# EEZ_CF-DIC_r5B1.net
KiCad netlist of a schematic drawn in EAGLE
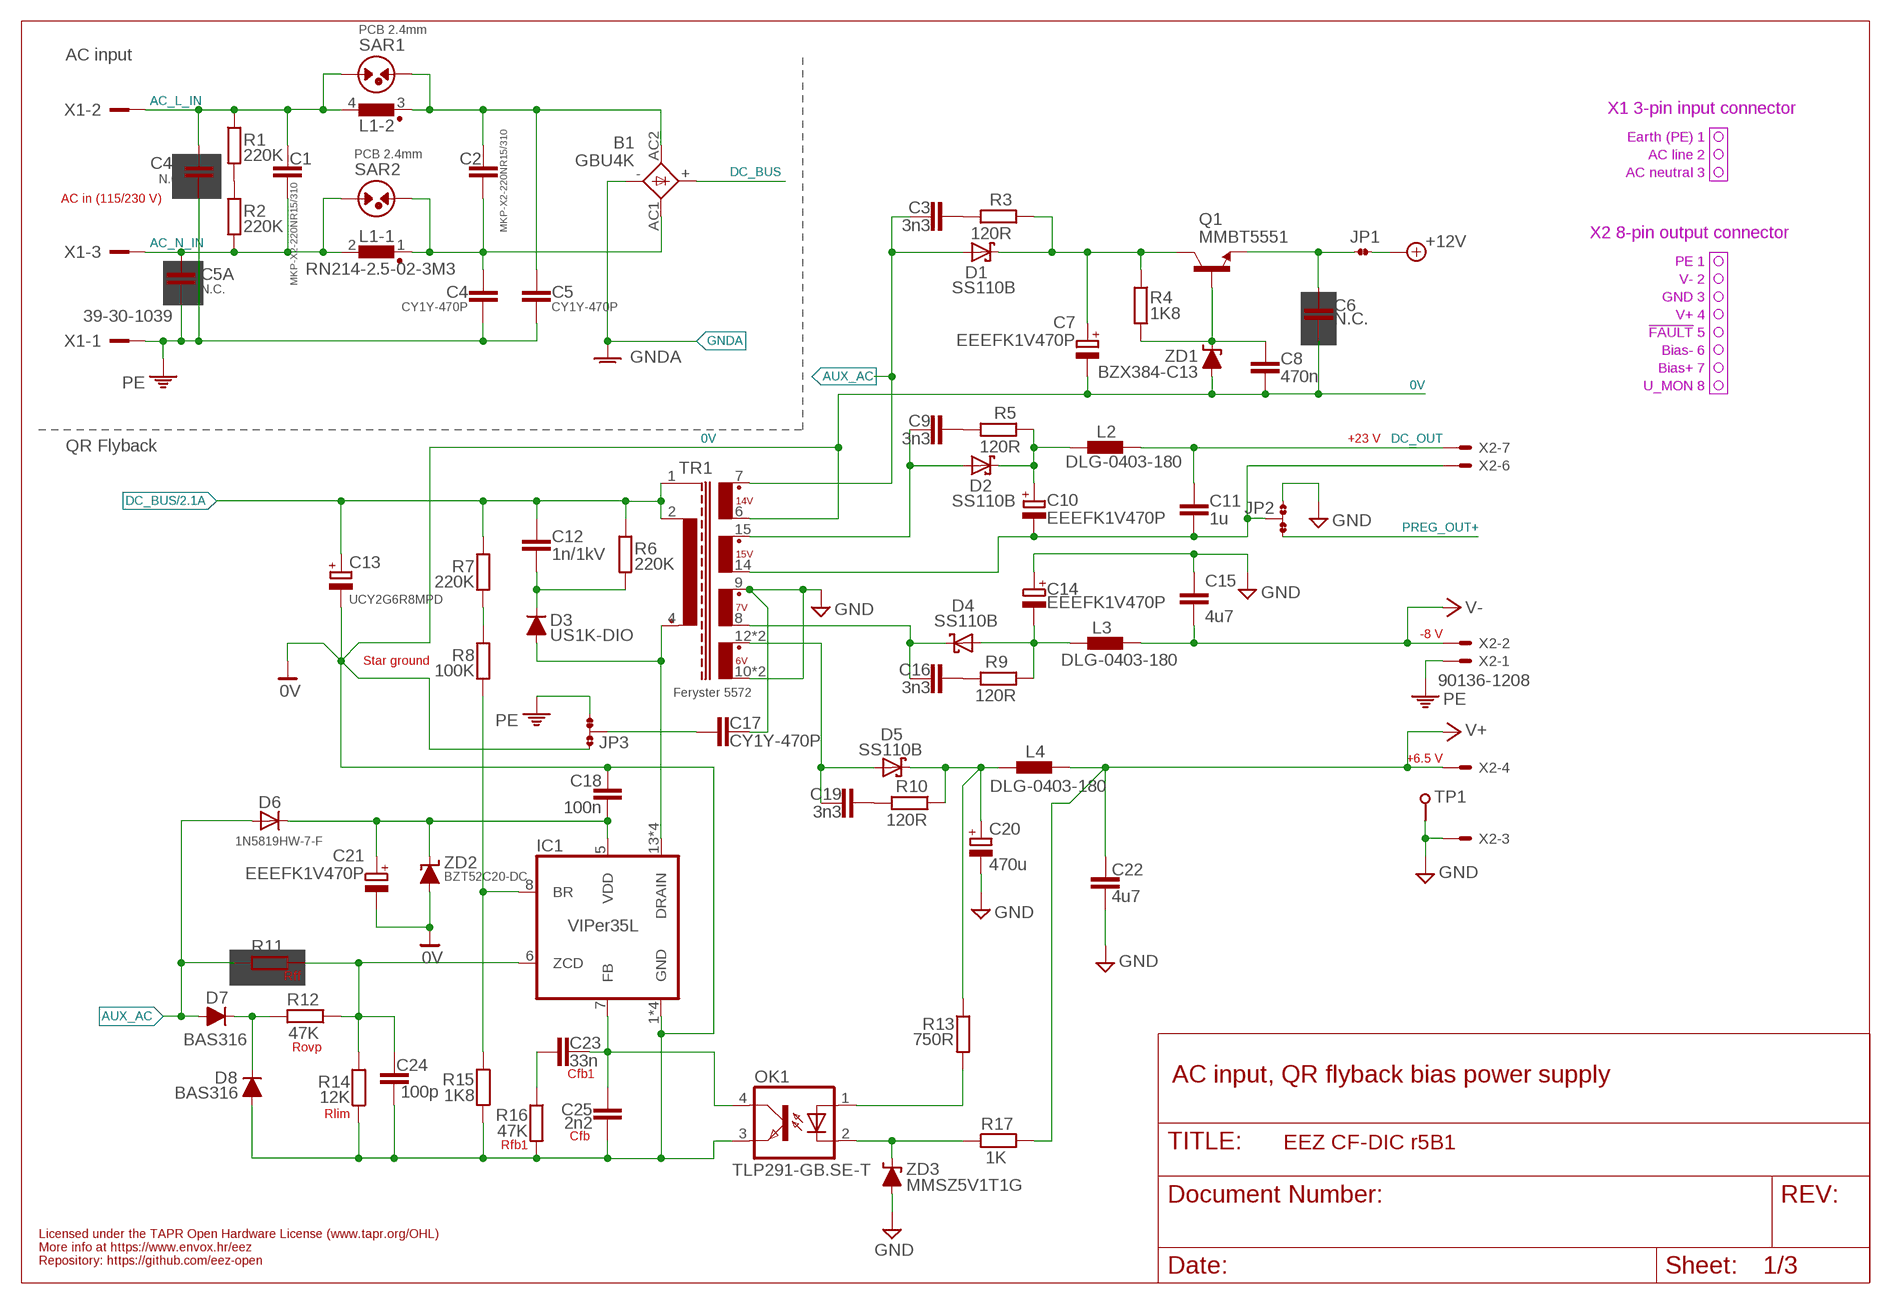
[diagram p0: schematic, sheet 1]
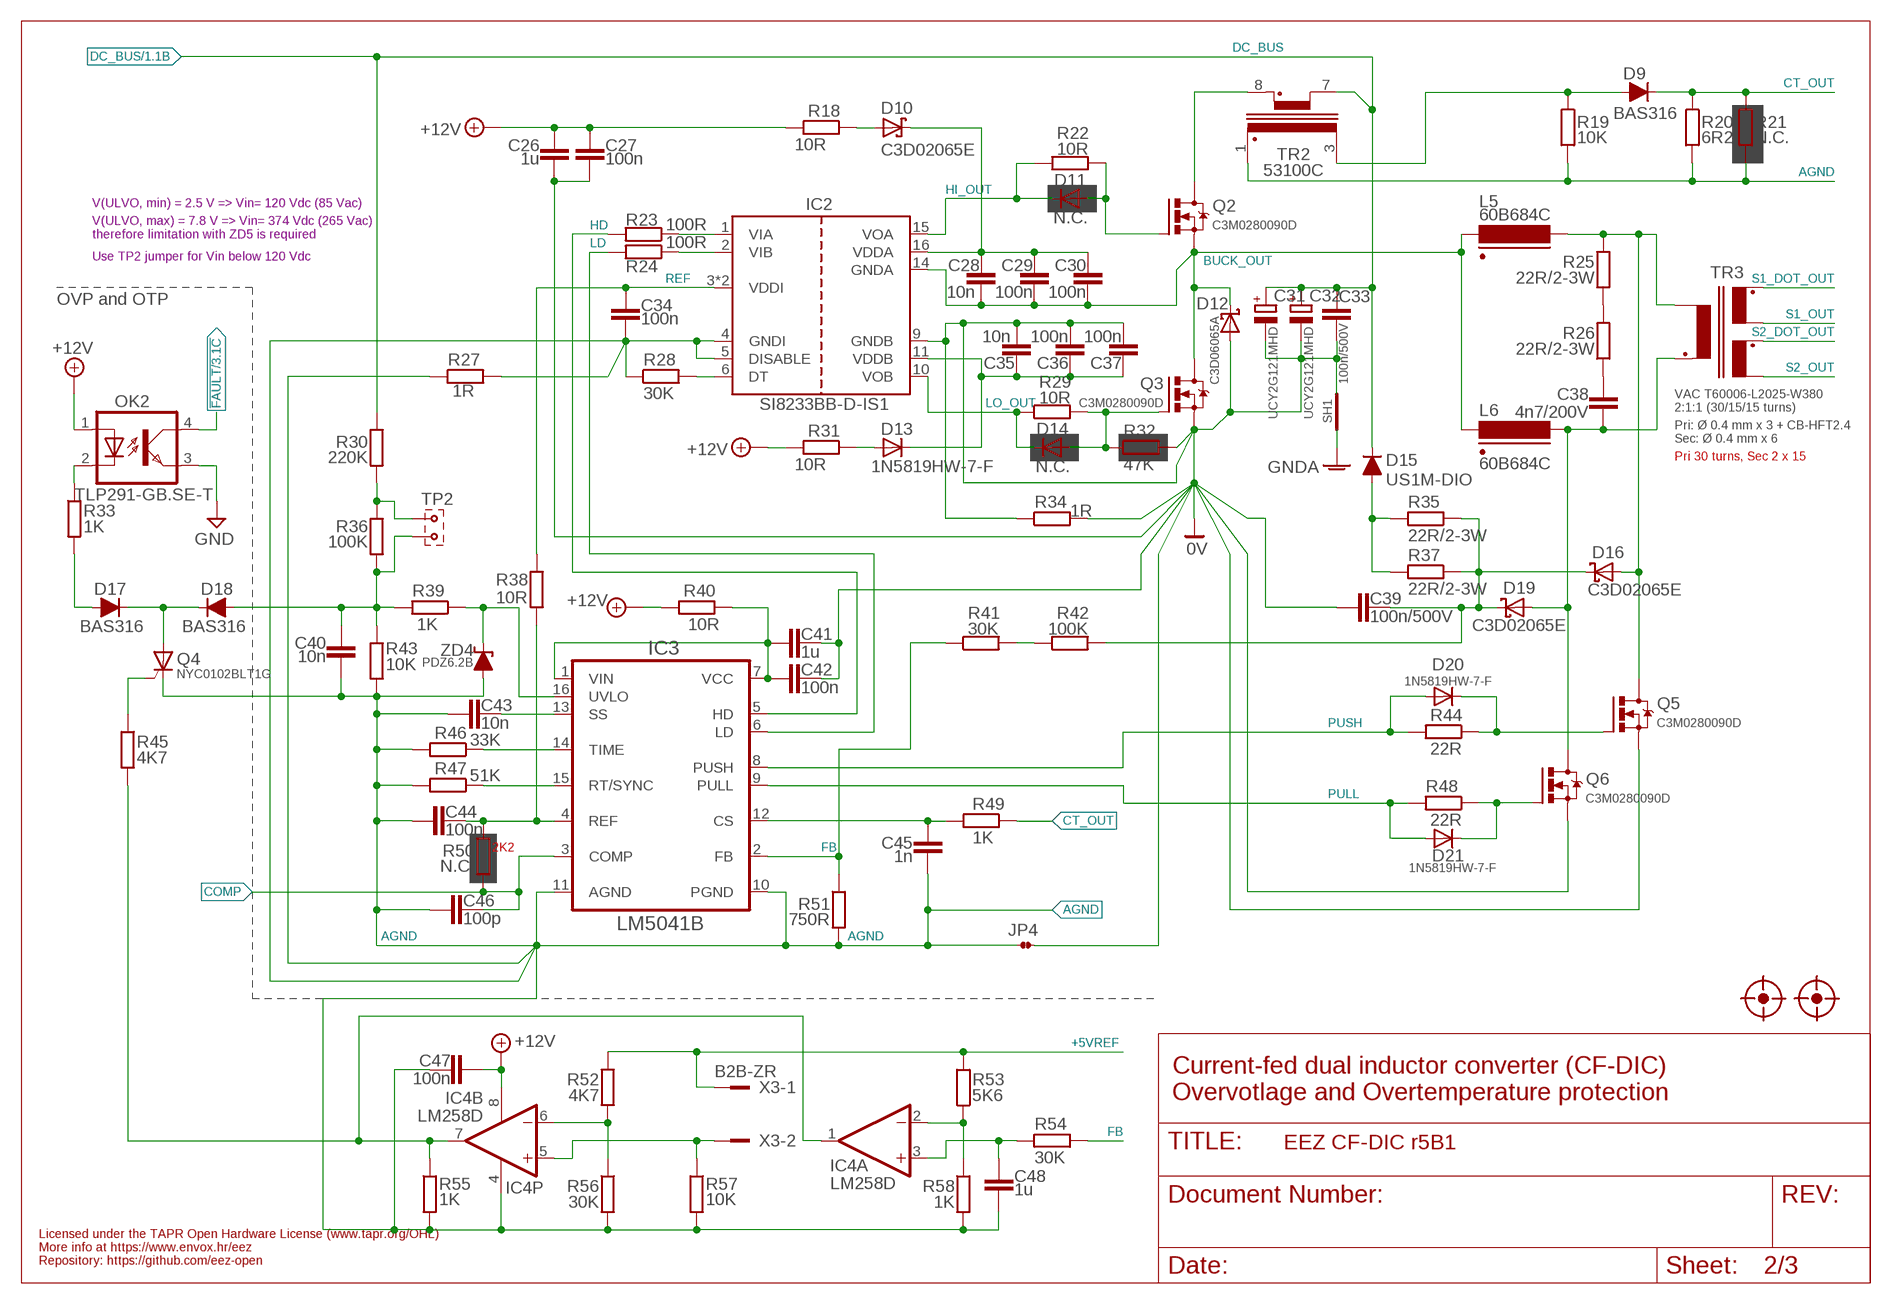
[diagram p1: schematic, sheet 2]
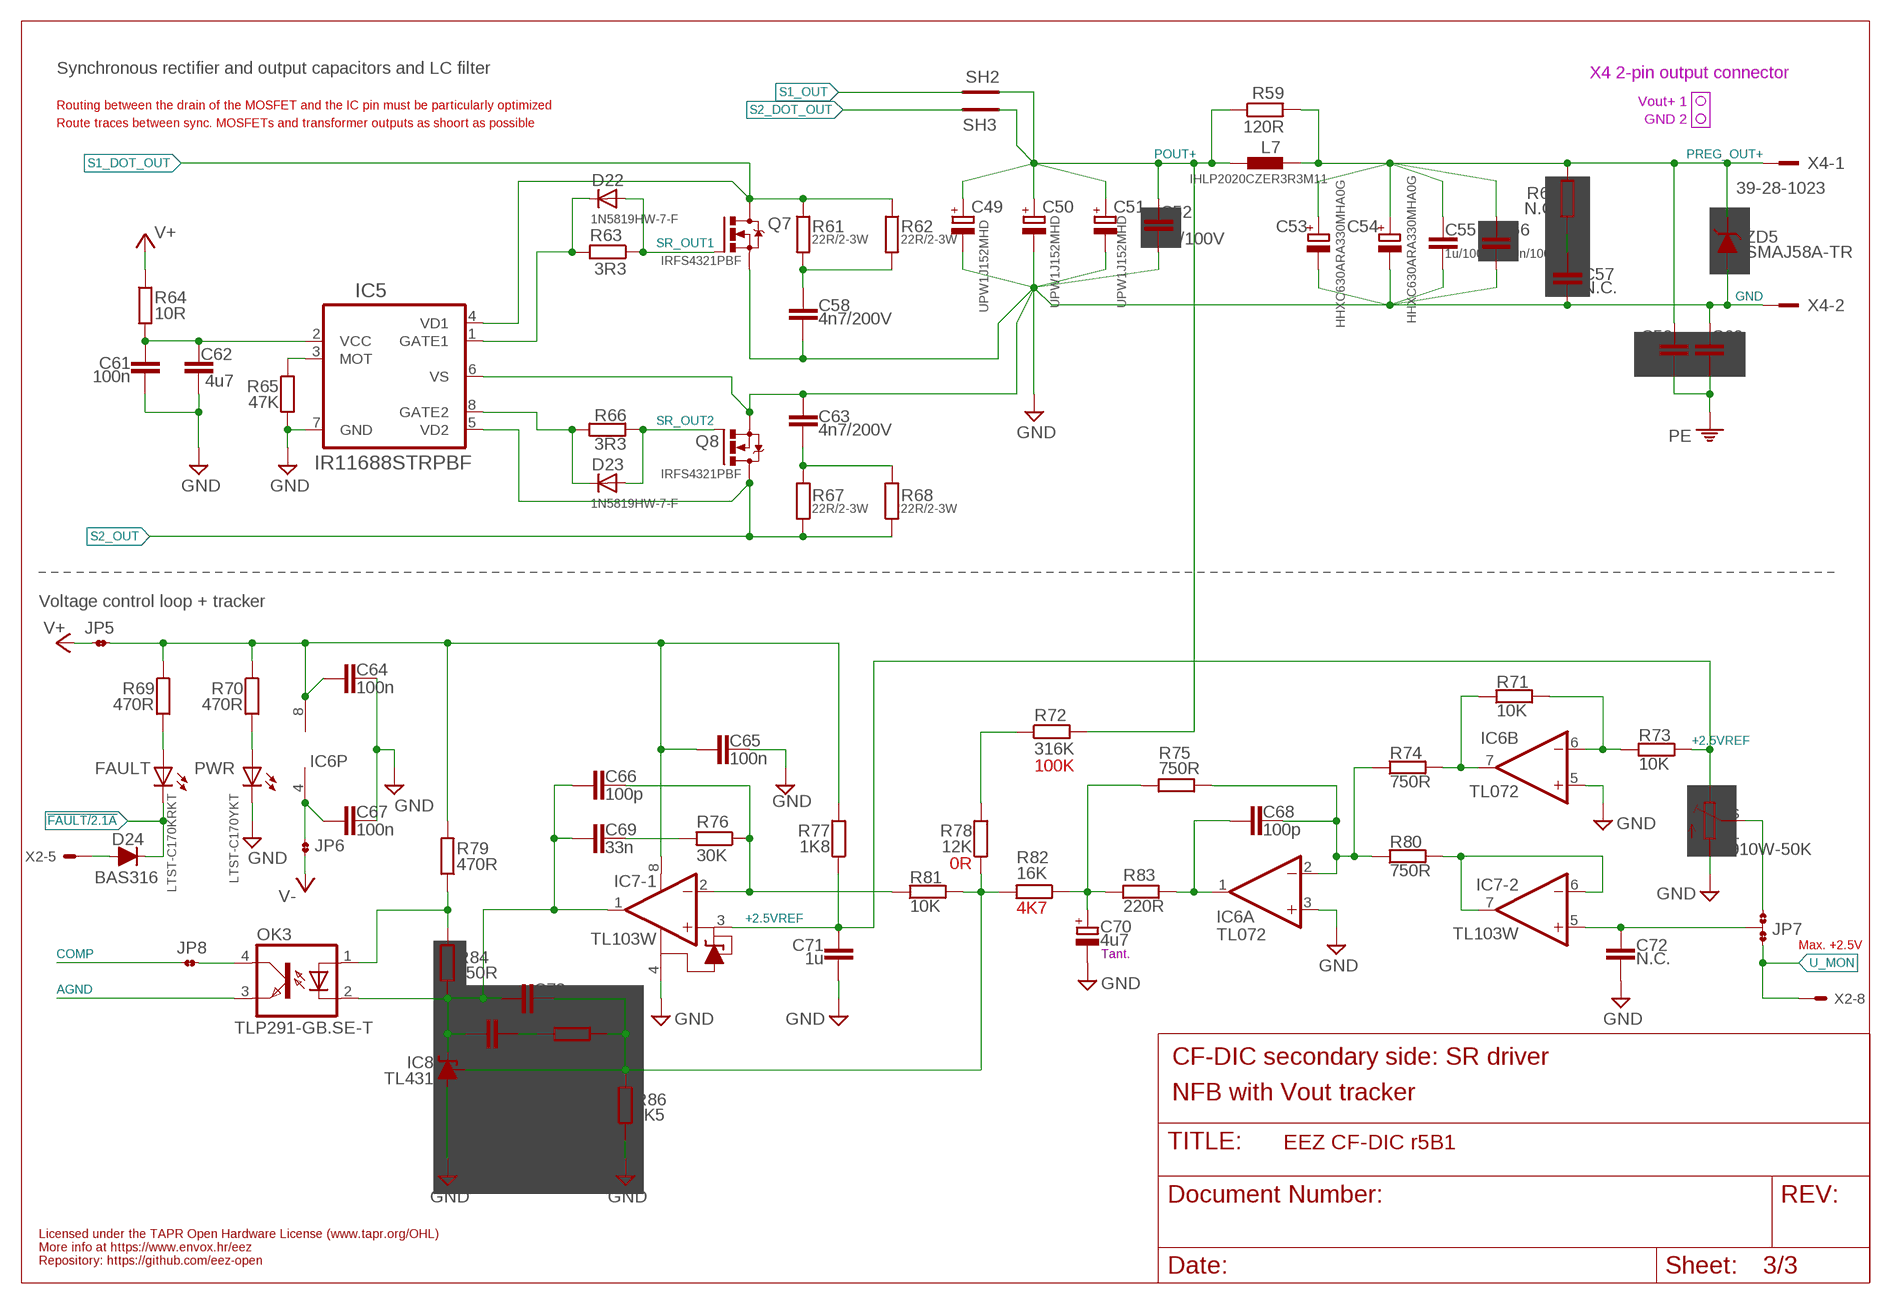
[diagram p2: schematic, sheet 3]

(export (version "E")
  (design (tool "Eeschema 10.0.6"))
  (components
    (comp (ref "C26")
      (value "1u")
      (footprint "eagle-import:C0805")
      (libsource (lib "eagle-import") (part "C-EUC0805"))
    )
    (comp (ref "C27")
      (value "100n")
      (footprint "eagle-import:C0603")
      (libsource (lib "eagle-import") (part "C-EUC0603"))
    )
    (comp (ref "C28")
      (value "10n")
      (footprint "eagle-import:C0603")
      (libsource (lib "eagle-import") (part "C-EUC0603"))
    )
    (comp (ref "C29")
      (value "100n")
      (footprint "eagle-import:C0603")
      (libsource (lib "eagle-import") (part "C-EUC0603"))
    )
    (comp (ref "C30")
      (value "100n")
      (footprint "eagle-import:C0603")
      (libsource (lib "eagle-import") (part "C-EUC0603"))
    )
    (comp (ref "C31")
      (value "UCY2G121MHD")
      (footprint "eagle-import:ECAP7.5_18")
      (libsource (lib "eagle-import") (part "ECAP7.5G_18MM"))
    )
    (comp (ref "C32")
      (value "UCY2G121MHD")
      (footprint "eagle-import:ECAP7.5_18")
      (libsource (lib "eagle-import") (part "ECAP7.5G_18MM"))
    )
    (comp (ref "C33")
      (value "100n/500V")
      (footprint "eagle-import:C1812")
      (libsource (lib "eagle-import") (part "C-EUC1812"))
    )
    (comp (ref "C34")
      (value "100n")
      (footprint "eagle-import:C0603")
      (libsource (lib "eagle-import") (part "C-EUC0603"))
    )
    (comp (ref "C35")
      (value "10n")
      (footprint "eagle-import:C0603")
      (libsource (lib "eagle-import") (part "C-EUC0603"))
    )
    (comp (ref "C36")
      (value "100n")
      (footprint "eagle-import:C0603")
      (libsource (lib "eagle-import") (part "C-EUC0603"))
    )
    (comp (ref "C37")
      (value "100n")
      (footprint "eagle-import:C0603")
      (libsource (lib "eagle-import") (part "C-EUC0603"))
    )
    (comp (ref "C38")
      (value "4n7/200V")
      (footprint "eagle-import:C1210")
      (libsource (lib "eagle-import") (part "C-EUC1210"))
    )
    (comp (ref "C39")
      (value "100n/500V")
      (footprint "eagle-import:C1812")
      (libsource (lib "eagle-import") (part "C-EUC1812"))
    )
    (comp (ref "C40")
      (value "10n")
      (footprint "eagle-import:C0805")
      (libsource (lib "eagle-import") (part "C-EUC0805"))
    )
    (comp (ref "C41")
      (value "1u")
      (footprint "eagle-import:C0805")
      (libsource (lib "eagle-import") (part "C-EUC0805"))
    )
    (comp (ref "C42")
      (value "100n")
      (footprint "eagle-import:C0603")
      (libsource (lib "eagle-import") (part "C-EUC0603"))
    )
    (comp (ref "C43")
      (value "10n")
      (footprint "eagle-import:C0805")
      (libsource (lib "eagle-import") (part "C-EUC0805"))
    )
    (comp (ref "C44")
      (value "100n")
      (footprint "eagle-import:C0603")
      (libsource (lib "eagle-import") (part "C-EUC0603"))
    )
    (comp (ref "C45")
      (value "1n")
      (footprint "eagle-import:C0805")
      (libsource (lib "eagle-import") (part "C-EUC0805"))
    )
    (comp (ref "C46")
      (value "100p")
      (footprint "eagle-import:C0805")
      (libsource (lib "eagle-import") (part "C-EUC0805"))
    )
    (comp (ref "C47")
      (value "100n")
      (footprint "eagle-import:C0603")
      (libsource (lib "eagle-import") (part "C-EUC0603"))
    )
    (comp (ref "C48")
      (value "1u")
      (footprint "eagle-import:C0805")
      (libsource (lib "eagle-import") (part "C-EUC0805"))
    )
    (comp (ref "D9")
      (value "BAS316")
      (footprint "eagle-import:SOD323-R")
      (libsource (lib "eagle-import") (part "DIODESOD323R"))
    )
    (comp (ref "D10")
      (value "C3D02065E")
      (footprint "eagle-import:TO252")
      (libsource (lib "eagle-import") (part "SCHOTTKY-SIC"))
    )
    (comp (ref "D11")
      (value "N.C.")
      (footprint "eagle-import:SOD323-W")
      (libsource (lib "eagle-import") (part "DIODE-SOD323-W"))
    )
    (comp (ref "D12")
      (value "C3D06065A")
      (footprint "eagle-import:TO220-2")
      (libsource (lib "eagle-import") (part "SCHOTTKY-TO220"))
    )
    (comp (ref "D13")
      (value "1N5819HW-7-F")
      (footprint "eagle-import:SOD323-W")
      (libsource (lib "eagle-import") (part "DIODE-SOD323-W"))
    )
    (comp (ref "D14")
      (value "N.C.")
      (footprint "eagle-import:SOD323-W")
      (libsource (lib "eagle-import") (part "DIODE-SOD323-W"))
    )
    (comp (ref "D15")
      (value "US1M-DIO")
      (footprint "eagle-import:DO214AA")
      (libsource (lib "eagle-import") (part "DIODEDO214AA"))
    )
    (comp (ref "D16")
      (value "C3D02065E")
      (footprint "eagle-import:TO252")
      (libsource (lib "eagle-import") (part "SCHOTTKY-SIC"))
    )
    (comp (ref "D17")
      (value "BAS316")
      (footprint "eagle-import:SOD323-R")
      (libsource (lib "eagle-import") (part "DIODESOD323R"))
    )
    (comp (ref "D18")
      (value "BAS316")
      (footprint "eagle-import:SOD323-R")
      (libsource (lib "eagle-import") (part "DIODESOD323R"))
    )
    (comp (ref "D19")
      (value "C3D02065E")
      (footprint "eagle-import:TO252")
      (libsource (lib "eagle-import") (part "SCHOTTKY-SIC"))
    )
    (comp (ref "D20")
      (value "1N5819HW-7-F")
      (footprint "eagle-import:SOD323-W")
      (libsource (lib "eagle-import") (part "DIODE-SOD323-W"))
    )
    (comp (ref "D21")
      (value "1N5819HW-7-F")
      (footprint "eagle-import:SOD323-W")
      (libsource (lib "eagle-import") (part "DIODE-SOD323-W"))
    )
    (comp (ref "FM1")
      (value "FIDUCIAL_2")
      (footprint "eagle-import:FIDUCIAL_DUAL")
      (libsource (lib "eagle-import") (part "FIDUCIAL_2"))
    )
    (comp (ref "FM2")
      (value "FIDUCIAL_2")
      (footprint "eagle-import:FIDUCIAL_DUAL")
      (libsource (lib "eagle-import") (part "FIDUCIAL_2"))
    )
    (comp (ref "IC2")
      (value "SI8233BB-D-IS1")
      (footprint "eagle-import:SOIC-16")
      (libsource (lib "eagle-import") (part "SI8233"))
    )
    (comp (ref "IC3")
      (value "LM5041B")
      (footprint "eagle-import:MTC16")
      (fields (field (name "MANUFACTURER_PART_NUMBER") "lm5041mtcnopb"))
      (libsource (lib "eagle-import") (part "LM5041"))
    )
    (comp (ref "IC4")
      (value "LM258D")
      (footprint "eagle-import:SOIC127P600X173-8N")
      (libsource (lib "eagle-import") (part "TL072SOIC8"))
    )
    (comp (ref "JP4")
      (value "JP2-NOCUT")
      (footprint "eagle-import:JP2-NOCUT")
      (libsource (lib "eagle-import") (part "JP2-NOCUT"))
    )
    (comp (ref "L5")
      (value "60B684C")
      (footprint "eagle-import:MURATA_6000B")
      (libsource (lib "eagle-import") (part "MURATA_6000B"))
    )
    (comp (ref "L6")
      (value "60B684C")
      (footprint "eagle-import:MURATA_6000B")
      (libsource (lib "eagle-import") (part "MURATA_6000B"))
    )
    (comp (ref "OK2")
      (value "TLP291-GB.SE-T")
      (footprint "eagle-import:SO4")
      (libsource (lib "eagle-import") (part "TLP291"))
    )
    (comp (ref "Q2")
      (value "C3M0280090D")
      (footprint "eagle-import:TO247BV")
      (libsource (lib "eagle-import") (part "IRFP240"))
    )
    (comp (ref "Q3")
      (value "C3M0280090D")
      (footprint "eagle-import:TO247BV")
      (libsource (lib "eagle-import") (part "IRFP240"))
    )
    (comp (ref "Q4")
      (value "NYC0102BLT1G")
      (footprint "eagle-import:SOT23")
      (libsource (lib "eagle-import") (part "NYC0102BLT1G"))
    )
    (comp (ref "Q5")
      (value "C3M0280090D")
      (footprint "eagle-import:TO247BV")
      (libsource (lib "eagle-import") (part "IRFP240"))
    )
    (comp (ref "Q6")
      (value "C3M0280090D")
      (footprint "eagle-import:TO247BV")
      (libsource (lib "eagle-import") (part "IRFP240"))
    )
    (comp (ref "R18")
      (value "10R")
      (footprint "eagle-import:R0805")
      (libsource (lib "eagle-import") (part "R-EU_R0805"))
    )
    (comp (ref "R19")
      (value "10K")
      (footprint "eagle-import:R0805")
      (libsource (lib "eagle-import") (part "R-EU_R0805"))
    )
    (comp (ref "R20")
      (value "6R2")
      (footprint "eagle-import:R0805")
      (libsource (lib "eagle-import") (part "R-EU_R0805"))
    )
    (comp (ref "R21")
      (value "N.C.")
      (footprint "eagle-import:R0805")
      (libsource (lib "eagle-import") (part "R-EU_R0805"))
    )
    (comp (ref "R22")
      (value "10R")
      (footprint "eagle-import:R0805")
      (libsource (lib "eagle-import") (part "R-EU_R0805"))
    )
    (comp (ref "R23")
      (value "100R")
      (footprint "eagle-import:R0805")
      (libsource (lib "eagle-import") (part "R-EU_R0805"))
    )
    (comp (ref "R24")
      (value "100R")
      (footprint "eagle-import:R0805")
      (libsource (lib "eagle-import") (part "R-EU_R0805"))
    )
    (comp (ref "R25")
      (value "22R/2-3W")
      (footprint "eagle-import:R2512")
      (libsource (lib "eagle-import") (part "R-EU_R2512"))
    )
    (comp (ref "R26")
      (value "22R/2-3W")
      (footprint "eagle-import:R2512")
      (libsource (lib "eagle-import") (part "R-EU_R2512"))
    )
    (comp (ref "R27")
      (value "1R")
      (footprint "eagle-import:R0805")
      (libsource (lib "eagle-import") (part "R-EU_R0805"))
    )
    (comp (ref "R28")
      (value "30K")
      (footprint "eagle-import:R0805")
      (libsource (lib "eagle-import") (part "R-EU_R0805"))
    )
    (comp (ref "R29")
      (value "10R")
      (footprint "eagle-import:R0805")
      (libsource (lib "eagle-import") (part "R-EU_R0805"))
    )
    (comp (ref "R30")
      (value "220K")
      (footprint "eagle-import:R1206")
      (libsource (lib "eagle-import") (part "R-EU_R1206"))
    )
    (comp (ref "R31")
      (value "10R")
      (footprint "eagle-import:R0805")
      (libsource (lib "eagle-import") (part "R-EU_R0805"))
    )
    (comp (ref "R32")
      (value "47K")
      (footprint "eagle-import:R0805")
      (libsource (lib "eagle-import") (part "R-EU_R0805"))
    )
    (comp (ref "R33")
      (value "1K")
      (footprint "eagle-import:R0805")
      (libsource (lib "eagle-import") (part "R-EU_R0805"))
    )
    (comp (ref "R34")
      (value "1R")
      (footprint "eagle-import:R0805")
      (libsource (lib "eagle-import") (part "R-EU_R0805"))
    )
    (comp (ref "R35")
      (value "22R/2-3W")
      (footprint "eagle-import:R2512")
      (libsource (lib "eagle-import") (part "R-EU_R2512"))
    )
    (comp (ref "R36")
      (value "100K")
      (footprint "eagle-import:R0805")
      (libsource (lib "eagle-import") (part "R-EU_R0805"))
    )
    (comp (ref "R37")
      (value "22R/2-3W")
      (footprint "eagle-import:R2512")
      (libsource (lib "eagle-import") (part "R-EU_R2512"))
    )
    (comp (ref "R38")
      (value "10R")
      (footprint "eagle-import:R0805")
      (libsource (lib "eagle-import") (part "R-EU_R0805"))
    )
    (comp (ref "R39")
      (value "1K")
      (footprint "eagle-import:R0805")
      (libsource (lib "eagle-import") (part "R-EU_R0805"))
    )
    (comp (ref "R40")
      (value "10R")
      (footprint "eagle-import:R0805")
      (libsource (lib "eagle-import") (part "R-EU_R0805"))
    )
    (comp (ref "R41")
      (value "30K")
      (footprint "eagle-import:R0805")
      (libsource (lib "eagle-import") (part "R-EU_R0805"))
    )
    (comp (ref "R42")
      (value "100K")
      (footprint "eagle-import:R0805")
      (libsource (lib "eagle-import") (part "R-EU_R0805"))
    )
    (comp (ref "R43")
      (value "10K")
      (footprint "eagle-import:R0805")
      (libsource (lib "eagle-import") (part "R-EU_R0805"))
    )
    (comp (ref "R44")
      (value "22R")
      (footprint "eagle-import:R0805")
      (libsource (lib "eagle-import") (part "R-EU_R0805"))
    )
    (comp (ref "R45")
      (value "4K7")
      (footprint "eagle-import:R0805")
      (libsource (lib "eagle-import") (part "R-EU_R0805"))
    )
    (comp (ref "R46")
      (value "33K")
      (footprint "eagle-import:R0805")
      (libsource (lib "eagle-import") (part "R-EU_R0805"))
    )
    (comp (ref "R47")
      (value "51K")
      (footprint "eagle-import:R0805")
      (libsource (lib "eagle-import") (part "R-EU_R0805"))
    )
    (comp (ref "R48")
      (value "22R")
      (footprint "eagle-import:R0805")
      (libsource (lib "eagle-import") (part "R-EU_R0805"))
    )
    (comp (ref "R49")
      (value "1K")
      (footprint "eagle-import:R0805")
      (libsource (lib "eagle-import") (part "R-EU_R0805"))
    )
    (comp (ref "R50")
      (value "N.C.")
      (footprint "eagle-import:R0805")
      (libsource (lib "eagle-import") (part "R-EU_R0805"))
    )
    (comp (ref "R51")
      (value "750R")
      (footprint "eagle-import:R0805")
      (libsource (lib "eagle-import") (part "R-EU_R0805"))
    )
    (comp (ref "R52")
      (value "4K7")
      (footprint "eagle-import:R0805")
      (libsource (lib "eagle-import") (part "R-EU_R0805"))
    )
    (comp (ref "R53")
      (value "5K6")
      (footprint "eagle-import:R0805")
      (libsource (lib "eagle-import") (part "R-EU_R0805"))
    )
    (comp (ref "R54")
      (value "30K")
      (footprint "eagle-import:R0805")
      (libsource (lib "eagle-import") (part "R-EU_R0805"))
    )
    (comp (ref "R55")
      (value "1K")
      (footprint "eagle-import:R0805")
      (libsource (lib "eagle-import") (part "R-EU_R0805"))
    )
    (comp (ref "R56")
      (value "30K")
      (footprint "eagle-import:R0805")
      (libsource (lib "eagle-import") (part "R-EU_R0805"))
    )
    (comp (ref "R57")
      (value "10K")
      (footprint "eagle-import:R0805")
      (libsource (lib "eagle-import") (part "R-EU_R0805"))
    )
    (comp (ref "R58")
      (value "1K")
      (footprint "eagle-import:R0805")
      (libsource (lib "eagle-import") (part "R-EU_R0805"))
    )
    (comp (ref "SH1")
      (value "SHORTNOHOLE")
      (footprint "eagle-import:SHORT_NOHOLE")
      (libsource (lib "eagle-import") (part "SHORTNOHOLE"))
    )
    (comp (ref "TP2")
      (value "JUMPER-2PIN-2MM")
      (footprint "eagle-import:2MM-2")
      (libsource (lib "eagle-import") (part "JUMPER-2PIN-2MM"))
    )
    (comp (ref "TR2")
      (value "53100C")
      (footprint "eagle-import:MURATA_5300")
      (libsource (lib "eagle-import") (part "MURATA_5300"))
    )
    (comp (ref "TR3")
      (value "VAC T60006-L2025-W380")
      (footprint "eagle-import:VAC_DUAL_SEC")
      (libsource (lib "eagle-import") (part "PCB_TRAFO_FLYBACK2-VAC"))
    )
    (comp (ref "X3")
      (value "B2B-ZR")
      (footprint "eagle-import:B2B-ZR")
      (libsource (lib "eagle-import") (part "B2B-ZR"))
    )
    (comp (ref "ZD4")
      (value "PDZ6.2B")
      (footprint "eagle-import:SOD323-W")
      (libsource (lib "eagle-import") (part "ZENER-DIODESOD323"))
    )
    (comp (ref "C49")
      (value "UPW1J152MHD")
      (footprint "eagle-import:ECAP7.5_18")
      (libsource (lib "eagle-import") (part "ECAP7.5G_18MM"))
    )
    (comp (ref "C50")
      (value "UPW1J152MHD")
      (footprint "eagle-import:ECAP7.5_18")
      (libsource (lib "eagle-import") (part "ECAP7.5G_18MM"))
    )
    (comp (ref "C51")
      (value "UPW1J152MHD")
      (footprint "eagle-import:ECAP7.5_18")
      (libsource (lib "eagle-import") (part "ECAP7.5G_18MM"))
    )
    (comp (ref "C52")
      (value "1u/100V")
      (footprint "eagle-import:C1206")
      (libsource (lib "eagle-import") (part "C-EUC1206"))
    )
    (comp (ref "C53")
      (value "HHXC630ARA330MHA0G ")
      (footprint "eagle-import:CAPAE830X1050N")
      (fields
        (field (name "MPN") "EEE-FK1J470P")
        (field (name "TOLERANCE") "±20 %")
        (field (name "MPN_1") "EEE-FK1J470P")
        (field (name "OC_FARNELL") "9696032  ")
        (field (name "OC_NEWARK") "96K9403")
        (field (name "PACKAGE") "CASE-F")
        (field (name "SUPPLIER") "PANASONIC")
        (field (name "TOLERANCE_1") "±20 %")
        (field (name "VOLTAGERATING") "63 V")
      )
      (libsource (lib "eagle-import") (part "EEE--CASE-FFK1J470P"))
    )
    (comp (ref "C54")
      (value "HHXC630ARA330MHA0G")
      (footprint "eagle-import:CAPAE830X1050N")
      (fields (field (name "MPN") "EEE-FK1J470P") (field (name "TOLERANCE") "±20 %"))
      (libsource (lib "eagle-import") (part "EEE--CASE-FFK1J470P"))
    )
    (comp (ref "C55")
      (value "1u/100V")
      (footprint "eagle-import:C1206")
      (libsource (lib "eagle-import") (part "C-EUC1206"))
    )
    (comp (ref "C56")
      (value "100n/100V")
      (footprint "eagle-import:C1206")
      (libsource (lib "eagle-import") (part "C-EUC1206"))
    )
    (comp (ref "C57")
      (value "N.C.")
      (footprint "eagle-import:C1206")
      (libsource (lib "eagle-import") (part "C-EUC1206"))
    )
    (comp (ref "C58")
      (value "4n7/200V")
      (footprint "eagle-import:C1206")
      (libsource (lib "eagle-import") (part "C-EUC1206"))
    )
    (comp (ref "C59")
      (value "N.C.")
      (footprint "eagle-import:C1206")
      (libsource (lib "eagle-import") (part "C-EUC1206"))
    )
    (comp (ref "C60")
      (value "N.C.")
      (footprint "eagle-import:C1206")
      (libsource (lib "eagle-import") (part "C-EUC1206"))
    )
    (comp (ref "C61")
      (value "100n")
      (footprint "eagle-import:C0603")
      (libsource (lib "eagle-import") (part "C-EUC0603"))
    )
    (comp (ref "C62")
      (value "4u7")
      (footprint "eagle-import:C1206")
      (libsource (lib "eagle-import") (part "C-EUC1206"))
    )
    (comp (ref "C63")
      (value "4n7/200V")
      (footprint "eagle-import:C1206")
      (libsource (lib "eagle-import") (part "C-EUC1206"))
    )
    (comp (ref "C64")
      (value "100n")
      (footprint "eagle-import:C0603")
      (libsource (lib "eagle-import") (part "C-EUC0603"))
    )
    (comp (ref "C65")
      (value "100n")
      (footprint "eagle-import:C0603")
      (libsource (lib "eagle-import") (part "C-EUC0603"))
    )
    (comp (ref "C66")
      (value "100p")
      (footprint "eagle-import:C0805")
      (libsource (lib "eagle-import") (part "C-EUC0805"))
    )
    (comp (ref "C67")
      (value "100n")
      (footprint "eagle-import:C0603")
      (libsource (lib "eagle-import") (part "C-EUC0603"))
    )
    (comp (ref "C68")
      (value "100p")
      (footprint "eagle-import:C0805")
      (libsource (lib "eagle-import") (part "C-EUC0805"))
    )
    (comp (ref "C69")
      (value "33n")
      (footprint "eagle-import:C0805")
      (libsource (lib "eagle-import") (part "C-EUC0805"))
    )
    (comp (ref "C70")
      (value "4u7")
      (footprint "eagle-import:EC1206")
      (libsource (lib "eagle-import") (part "ECAP1206"))
    )
    (comp (ref "C71")
      (value "1u")
      (footprint "eagle-import:C0805")
      (libsource (lib "eagle-import") (part "C-EUC0805"))
    )
    (comp (ref "C72")
      (value "N.C.")
      (footprint "eagle-import:C0805")
      (libsource (lib "eagle-import") (part "C-EUC0805"))
    )
    (comp (ref "C73")
      (value "N.C.")
      (footprint "eagle-import:C0805")
      (libsource (lib "eagle-import") (part "C-EUC0805"))
    )
    (comp (ref "C74")
      (value "1n")
      (footprint "eagle-import:C0805")
      (libsource (lib "eagle-import") (part "C-EUC0805"))
    )
    (comp (ref "D22")
      (value "1N5819HW-7-F")
      (footprint "eagle-import:SOD323-W")
      (libsource (lib "eagle-import") (part "DIODE-SOD323-W"))
    )
    (comp (ref "D23")
      (value "1N5819HW-7-F")
      (footprint "eagle-import:SOD323-W")
      (libsource (lib "eagle-import") (part "DIODE-SOD323-W"))
    )
    (comp (ref "D24")
      (value "BAS316")
      (footprint "eagle-import:SOD323-R")
      (libsource (lib "eagle-import") (part "DIODESOD323R"))
    )
    (comp (ref "FAULT")
      (value "LTST-C170KRKT")
      (footprint "eagle-import:LED_0805")
      (libsource (lib "eagle-import") (part "LED0805"))
    )
    (comp (ref "IC5")
      (value "IR11688STRPBF")
      (footprint "eagle-import:SO8")
      (libsource (lib "eagle-import") (part "IR11688"))
    )
    (comp (ref "IC6")
      (value "TL072")
      (footprint "eagle-import:SOIC127P600X173-8N")
      (libsource (lib "eagle-import") (part "TL072SOIC8"))
    )
    (comp (ref "IC7")
      (value "TL103W")
      (footprint "eagle-import:SOIC127P600X173-8N")
      (libsource (lib "eagle-import") (part "TL103W"))
    )
    (comp (ref "IC8")
      (value "TL431")
      (footprint "eagle-import:SOT103P240X110-3N")
      (libsource (lib "eagle-import") (part "TL431"))
    )
    (comp (ref "JP5")
      (value "JP2-NOCUT")
      (footprint "eagle-import:JP2-NOCUT")
      (libsource (lib "eagle-import") (part "JP2-NOCUT"))
    )
    (comp (ref "JP6")
      (value "JP2-NOCUT")
      (footprint "eagle-import:JP2-NOCUT")
      (libsource (lib "eagle-import") (part "JP2-NOCUT"))
    )
    (comp (ref "JP7")
      (value "JP3-CUT")
      (footprint "eagle-import:JP3-CUT")
      (libsource (lib "eagle-import") (part "JP3-CUT"))
    )
    (comp (ref "JP8")
      (value "JP2-NOCUT")
      (footprint "eagle-import:JP2-NOCUT")
      (libsource (lib "eagle-import") (part "JP2-NOCUT"))
    )
    (comp (ref "L7")
      (value "IHLP2020CZER3R3M11")
      (footprint "eagle-import:IHLP-2020BZ-11")
      (libsource (lib "eagle-import") (part "EEZ_inductors_and_transformers_IHLP-2020BZ-11"))
    )
    (comp (ref "OK3")
      (value "TLP291-GB.SE-T")
      (footprint "eagle-import:SO4")
      (libsource (lib "eagle-import") (part "TLP291"))
    )
    (comp (ref "P1")
      (value "T910W-50K")
      (footprint "eagle-import:S64W")
      (libsource (lib "eagle-import") (part "TPOT-S64W"))
    )
    (comp (ref "PWR")
      (value "LTST-C170YKT")
      (footprint "eagle-import:LED_0805")
      (libsource (lib "eagle-import") (part "LED0805"))
    )
    (comp (ref "Q7")
      (value "IRFS4321PBF")
      (footprint "eagle-import:TO263")
      (libsource (lib "eagle-import") (part "N-MOSFETTO263"))
    )
    (comp (ref "Q8")
      (value "IRFS4321PBF")
      (footprint "eagle-import:TO263")
      (libsource (lib "eagle-import") (part "N-MOSFETTO263"))
    )
    (comp (ref "R59")
      (value "120R")
      (footprint "eagle-import:R0805")
      (libsource (lib "eagle-import") (part "R-EU_R0805"))
    )
    (comp (ref "R60")
      (value "N.C.")
      (footprint "eagle-import:R1210")
      (libsource (lib "eagle-import") (part "R-EU_R1210"))
    )
    (comp (ref "R61")
      (value "22R/2-3W")
      (footprint "eagle-import:R2512")
      (libsource (lib "eagle-import") (part "R-EU_R2512"))
    )
    (comp (ref "R62")
      (value "22R/2-3W")
      (footprint "eagle-import:R2512")
      (libsource (lib "eagle-import") (part "R-EU_R2512"))
    )
    (comp (ref "R63")
      (value "3R3")
      (footprint "eagle-import:R0805")
      (libsource (lib "eagle-import") (part "R-EU_R0805"))
    )
    (comp (ref "R64")
      (value "10R")
      (footprint "eagle-import:R0805")
      (libsource (lib "eagle-import") (part "R-EU_R0805"))
    )
    (comp (ref "R65")
      (value "47K")
      (footprint "eagle-import:R0805")
      (libsource (lib "eagle-import") (part "R-EU_R0805"))
    )
    (comp (ref "R66")
      (value "3R3")
      (footprint "eagle-import:R0805")
      (libsource (lib "eagle-import") (part "R-EU_R0805"))
    )
    (comp (ref "R67")
      (value "22R/2-3W")
      (footprint "eagle-import:R2512")
      (libsource (lib "eagle-import") (part "R-EU_R2512"))
    )
    (comp (ref "R68")
      (value "22R/2-3W")
      (footprint "eagle-import:R2512")
      (libsource (lib "eagle-import") (part "R-EU_R2512"))
    )
    (comp (ref "R69")
      (value "470R")
      (footprint "eagle-import:R0805")
      (libsource (lib "eagle-import") (part "R-EU_R0805"))
    )
    (comp (ref "R70")
      (value "470R")
      (footprint "eagle-import:R0805")
      (libsource (lib "eagle-import") (part "R-EU_R0805"))
    )
    (comp (ref "R71")
      (value "10K")
      (footprint "eagle-import:R0805")
      (libsource (lib "eagle-import") (part "R-EU_R0805"))
    )
    (comp (ref "R72")
      (value "316K")
      (footprint "eagle-import:R0805")
      (libsource (lib "eagle-import") (part "R-EU_R0805"))
    )
    (comp (ref "R73")
      (value "10K")
      (footprint "eagle-import:R0805")
      (libsource (lib "eagle-import") (part "R-EU_R0805"))
    )
    (comp (ref "R74")
      (value "750R")
      (footprint "eagle-import:R0805")
      (libsource (lib "eagle-import") (part "R-EU_R0805"))
    )
    (comp (ref "R75")
      (value "750R")
      (footprint "eagle-import:R0805")
      (libsource (lib "eagle-import") (part "R-EU_R0805"))
    )
    (comp (ref "R76")
      (value "30K")
      (footprint "eagle-import:R0805")
      (libsource (lib "eagle-import") (part "R-EU_R0805"))
    )
    (comp (ref "R77")
      (value "1K8")
      (footprint "eagle-import:R0805")
      (libsource (lib "eagle-import") (part "R-EU_R0805"))
    )
    (comp (ref "R78")
      (value "12K")
      (footprint "eagle-import:R0805")
      (libsource (lib "eagle-import") (part "R-EU_R0805"))
    )
    (comp (ref "R79")
      (value "470R")
      (footprint "eagle-import:R0805")
      (libsource (lib "eagle-import") (part "R-EU_R0805"))
    )
    (comp (ref "R80")
      (value "750R")
      (footprint "eagle-import:R0805")
      (libsource (lib "eagle-import") (part "R-EU_R0805"))
    )
    (comp (ref "R81")
      (value "10K")
      (footprint "eagle-import:R0805")
      (libsource (lib "eagle-import") (part "R-EU_R0805"))
    )
    (comp (ref "R82")
      (value "16K")
      (footprint "eagle-import:R0805")
      (libsource (lib "eagle-import") (part "R-EU_R0805"))
    )
    (comp (ref "R83")
      (value "220R")
      (footprint "eagle-import:R0805")
      (libsource (lib "eagle-import") (part "R-EU_R0805"))
    )
    (comp (ref "R84")
      (value "750R")
      (footprint "eagle-import:R0805")
      (libsource (lib "eagle-import") (part "R-EU_R0805"))
    )
    (comp (ref "R85")
      (value "6K8")
      (footprint "eagle-import:R0805")
      (libsource (lib "eagle-import") (part "R-EU_R0805"))
    )
    (comp (ref "R86")
      (value "7K5")
      (footprint "eagle-import:R0805")
      (libsource (lib "eagle-import") (part "R-EU_R0805"))
    )
    (comp (ref "SH2")
      (value "SHORTNOHOLE")
      (footprint "eagle-import:SHORT_NOHOLE")
      (libsource (lib "eagle-import") (part "SHORTNOHOLE"))
    )
    (comp (ref "SH3")
      (value "SHORTNOHOLE")
      (footprint "eagle-import:SHORT_NOHOLE")
      (libsource (lib "eagle-import") (part "SHORTNOHOLE"))
    )
    (comp (ref "X2")
      (value "90136-1208")
      (footprint "eagle-import:70543-08")
      (libsource (lib "eagle-import") (part "C-GRID-08-70543"))
    )
    (comp (ref "X4")
      (value "39-28-1023")
      (footprint "eagle-import:MINIFIT_5566-02A")
      (libsource (lib "eagle-import") (part "MINIFIT_5566-02A"))
    )
    (comp (ref "ZD5")
      (value "SMAJ58A-TR")
      (footprint "eagle-import:DO214AC")
      (libsource (lib "eagle-import") (part "PSMAXX"))
    )
    (comp (ref "B1")
      (value "GBU4K")
      (footprint "eagle-import:GBU4K_CRE")
      (libsource (lib "eagle-import") (part "BRIDGE-CREEPAGE"))
    )
    (comp (ref "C1")
      (value "MKP-X2-220NR15/310")
      (footprint "eagle-import:C150-072X183")
      (libsource (lib "eagle-import") (part "C-EU150-072X183"))
    )
    (comp (ref "C2")
      (value "MKP-X2-220NR15/310")
      (footprint "eagle-import:C150-072X183")
      (libsource (lib "eagle-import") (part "C-EU150-072X183"))
    )
    (comp (ref "C3")
      (value "3n3")
      (footprint "eagle-import:C0805")
      (libsource (lib "eagle-import") (part "C-EUC0805"))
    )
    (comp (ref "C4")
      (value "CY1Y-470P")
      (footprint "eagle-import:CY075-032X103")
      (libsource (lib "eagle-import") (part "C-EUCY"))
    )
    (comp (ref "C4A")
      (value "N.C.")
      (footprint "eagle-import:CY075-032X103")
      (libsource (lib "eagle-import") (part "C-EUCY"))
    )
    (comp (ref "C5")
      (value "CY1Y-470P")
      (footprint "eagle-import:CY075-032X103")
      (libsource (lib "eagle-import") (part "C-EUCY"))
    )
    (comp (ref "C5A")
      (value "N.C.")
      (footprint "eagle-import:CY075-032X103")
      (libsource (lib "eagle-import") (part "C-EUCY"))
    )
    (comp (ref "C6")
      (value "N.C.")
      (footprint "eagle-import:C0603")
      (libsource (lib "eagle-import") (part "C-EUC0603"))
    )
    (comp (ref "C7")
      (value "EEEFK1V470P")
      (footprint "eagle-import:CAPAE660X610N")
      (libsource (lib "eagle-import") (part "ECAPPANASONIC_H"))
    )
    (comp (ref "C8")
      (value "470n")
      (footprint "eagle-import:C0805")
      (libsource (lib "eagle-import") (part "C-EUC0805"))
    )
    (comp (ref "C9")
      (value "3n3")
      (footprint "eagle-import:C0805")
      (libsource (lib "eagle-import") (part "C-EUC0805"))
    )
    (comp (ref "C10")
      (value "EEEFK1V470P")
      (footprint "eagle-import:CAPAE660X610N")
      (libsource (lib "eagle-import") (part "ECAPPANASONIC_H"))
    )
    (comp (ref "C11")
      (value "1u")
      (footprint "eagle-import:C0805")
      (libsource (lib "eagle-import") (part "C-EUC0805"))
    )
    (comp (ref "C12")
      (value "1n/1kV")
      (footprint "eagle-import:C1210")
      (libsource (lib "eagle-import") (part "C-EUC1210"))
    )
    (comp (ref "C13")
      (value "UCY2G6R8MPD")
      (footprint "eagle-import:ECAP5_10.5")
      (libsource (lib "eagle-import") (part "ECAP5G_10.5MM"))
    )
    (comp (ref "C14")
      (value "EEEFK1V470P")
      (footprint "eagle-import:CAPAE660X610N")
      (libsource (lib "eagle-import") (part "ECAPPANASONIC_H"))
    )
    (comp (ref "C15")
      (value "4u7")
      (footprint "eagle-import:C1210")
      (libsource (lib "eagle-import") (part "C-EUC1210"))
    )
    (comp (ref "C16")
      (value "3n3")
      (footprint "eagle-import:C0805")
      (libsource (lib "eagle-import") (part "C-EUC0805"))
    )
    (comp (ref "C17")
      (value "CY1Y-470P")
      (footprint "eagle-import:CY075-032X103")
      (libsource (lib "eagle-import") (part "C-EUCY"))
    )
    (comp (ref "C18")
      (value "100n")
      (footprint "eagle-import:C0603")
      (libsource (lib "eagle-import") (part "C-EUC0603"))
    )
    (comp (ref "C19")
      (value "3n3")
      (footprint "eagle-import:C0805")
      (libsource (lib "eagle-import") (part "C-EUC0805"))
    )
    (comp (ref "C20")
      (value "470u")
      (footprint "eagle-import:ECAP5_13")
      (libsource (lib "eagle-import") (part "ECAP5G_13MM"))
    )
    (comp (ref "C21")
      (value "EEEFK1V470P")
      (footprint "eagle-import:CAPAE660X610N")
      (libsource (lib "eagle-import") (part "ECAPPANASONIC_H"))
    )
    (comp (ref "C22")
      (value "4u7")
      (footprint "eagle-import:C1210")
      (libsource (lib "eagle-import") (part "C-EUC1210"))
    )
    (comp (ref "C23")
      (value "33n")
      (footprint "eagle-import:C0805")
      (libsource (lib "eagle-import") (part "C-EUC0805"))
    )
    (comp (ref "C24")
      (value "100p")
      (footprint "eagle-import:C0805")
      (libsource (lib "eagle-import") (part "C-EUC0805"))
    )
    (comp (ref "C25")
      (value "2n2")
      (footprint "eagle-import:C0805")
      (libsource (lib "eagle-import") (part "C-EUC0805"))
    )
    (comp (ref "D1")
      (value "SS110B")
      (footprint "eagle-import:SMB")
      (libsource (lib "eagle-import") (part "SCHOTTKYSMB"))
    )
    (comp (ref "D2")
      (value "SS110B")
      (footprint "eagle-import:SMB")
      (libsource (lib "eagle-import") (part "SCHOTTKYSMB"))
    )
    (comp (ref "D3")
      (value "US1K-DIO")
      (footprint "eagle-import:DO214AA")
      (libsource (lib "eagle-import") (part "DIODEDO214AA"))
    )
    (comp (ref "D4")
      (value "SS110B")
      (footprint "eagle-import:SMB")
      (libsource (lib "eagle-import") (part "SCHOTTKYSMB"))
    )
    (comp (ref "D5")
      (value "SS110B")
      (footprint "eagle-import:SMB")
      (libsource (lib "eagle-import") (part "SCHOTTKYSMB"))
    )
    (comp (ref "D6")
      (value "1N5819HW-7-F")
      (footprint "eagle-import:SOD323-W")
      (libsource (lib "eagle-import") (part "DIODE-SOD323-W"))
    )
    (comp (ref "D7")
      (value "BAS316")
      (footprint "eagle-import:SOD323-R")
      (libsource (lib "eagle-import") (part "DIODESOD323R"))
    )
    (comp (ref "D8")
      (value "BAS316")
      (footprint "eagle-import:SOD323-R")
      (libsource (lib "eagle-import") (part "DIODESOD323R"))
    )
    (comp (ref "IC1")
      (value "VIPer35L")
      (footprint "eagle-import:SOIC-16")
      (libsource (lib "eagle-import") (part "VIPER35"))
    )
    (comp (ref "JP1")
      (value "JP2-NOCUT")
      (footprint "eagle-import:JP2-NOCUT")
      (libsource (lib "eagle-import") (part "JP2-NOCUT"))
    )
    (comp (ref "JP2")
      (value "JP3-CUT")
      (footprint "eagle-import:JP3-CUT")
      (libsource (lib "eagle-import") (part "JP3-CUT"))
    )
    (comp (ref "JP3")
      (value "JP3-CUT")
      (footprint "eagle-import:JP3-CUT")
      (libsource (lib "eagle-import") (part "JP3-CUT"))
    )
    (comp (ref "L1")
      (value "RN214-2.5-02-3M3")
      (footprint "eagle-import:RN214")
      (fields (field (name "FARNELL") "1191518"))
      (libsource (lib "eagle-import") (part "EEZ_inductors_and_transformers_RN214"))
    )
    (comp (ref "L2")
      (value "DLG-0403-180")
      (footprint "eagle-import:DE0403")
      (libsource (lib "eagle-import") (part "EEZ_inductors_and_transformers_DE0403"))
    )
    (comp (ref "L3")
      (value "DLG-0403-180")
      (footprint "eagle-import:DE0403")
      (libsource (lib "eagle-import") (part "EEZ_inductors_and_transformers_DE0403"))
    )
    (comp (ref "L4")
      (value "DLG-0403-180")
      (footprint "eagle-import:DE0403")
      (libsource (lib "eagle-import") (part "EEZ_inductors_and_transformers_DE0403"))
    )
    (comp (ref "OK1")
      (value "TLP291-GB.SE-T")
      (footprint "eagle-import:SO4")
      (libsource (lib "eagle-import") (part "TLP291"))
    )
    (comp (ref "Q1")
      (value "MMBT5551")
      (footprint "eagle-import:SOT23-BEC")
      (libsource (lib "eagle-import") (part "-NPN-SOT23-BECMMBT5551LT1"))
    )
    (comp (ref "R1")
      (value "220K")
      (footprint "eagle-import:R1206")
      (libsource (lib "eagle-import") (part "R-EU_R1206"))
    )
    (comp (ref "R2")
      (value "220K")
      (footprint "eagle-import:R1206")
      (libsource (lib "eagle-import") (part "R-EU_R1206"))
    )
    (comp (ref "R3")
      (value "120R")
      (footprint "eagle-import:R0805")
      (libsource (lib "eagle-import") (part "R-EU_R0805"))
    )
    (comp (ref "R4")
      (value "1K8")
      (footprint "eagle-import:R0805")
      (libsource (lib "eagle-import") (part "R-EU_R0805"))
    )
    (comp (ref "R5")
      (value "120R")
      (footprint "eagle-import:R0805")
      (libsource (lib "eagle-import") (part "R-EU_R0805"))
    )
    (comp (ref "R6")
      (value "220K")
      (footprint "eagle-import:R1206")
      (libsource (lib "eagle-import") (part "R-EU_R1206"))
    )
    (comp (ref "R7")
      (value "220K")
      (footprint "eagle-import:R1206")
      (libsource (lib "eagle-import") (part "R-EU_R1206"))
    )
    (comp (ref "R8")
      (value "100K")
      (footprint "eagle-import:R0805")
      (libsource (lib "eagle-import") (part "R-EU_R0805"))
    )
    (comp (ref "R9")
      (value "120R")
      (footprint "eagle-import:R0805")
      (libsource (lib "eagle-import") (part "R-EU_R0805"))
    )
    (comp (ref "R10")
      (value "120R")
      (footprint "eagle-import:R0805")
      (libsource (lib "eagle-import") (part "R-EU_R0805"))
    )
    (comp (ref "R11")
      (value "N.C.")
      (footprint "eagle-import:R0805")
      (libsource (lib "eagle-import") (part "R-EU_R0805"))
    )
    (comp (ref "R12")
      (value "47K")
      (footprint "eagle-import:R0805")
      (libsource (lib "eagle-import") (part "R-EU_R0805"))
    )
    (comp (ref "R13")
      (value "750R")
      (footprint "eagle-import:R0805")
      (libsource (lib "eagle-import") (part "R-EU_R0805"))
    )
    (comp (ref "R14")
      (value "12K")
      (footprint "eagle-import:R0805")
      (libsource (lib "eagle-import") (part "R-EU_R0805"))
    )
    (comp (ref "R15")
      (value "1K8")
      (footprint "eagle-import:R0805")
      (libsource (lib "eagle-import") (part "R-EU_R0805"))
    )
    (comp (ref "R16")
      (value "47K")
      (footprint "eagle-import:R0805")
      (libsource (lib "eagle-import") (part "R-EU_R0805"))
    )
    (comp (ref "R17")
      (value "1K")
      (footprint "eagle-import:R0805")
      (libsource (lib "eagle-import") (part "R-EU_R0805"))
    )
    (comp (ref "SAR1")
      (value "PCB 2.4mm")
      (footprint "eagle-import:PCB-SAR_2.4MM")
      (libsource (lib "eagle-import") (part "SARPCB-2.4MM"))
    )
    (comp (ref "SAR2")
      (value "PCB 2.4mm")
      (footprint "eagle-import:PCB-SAR_2.4MM")
      (libsource (lib "eagle-import") (part "SARPCB-2.4MM"))
    )
    (comp (ref "TP1")
      (value "PCB_TEST_TABSHIELD")
      (footprint "eagle-import:PCB_SHIELD_TAB")
      (libsource (lib "eagle-import") (part "PCB_TEST_TABSHIELD"))
    )
    (comp (ref "TR1")
      (value "Feryster 5572")
      (footprint "eagle-import:FERYSTER_5572")
      (libsource (lib "eagle-import") (part "EEZ_inductors_and_transformers_FERYSTER_5572"))
    )
    (comp (ref "X1")
      (value "39-30-1039")
      (footprint "eagle-import:MINIFIT_39301039_CRE")
      (libsource (lib "eagle-import") (part "MINIFIT_39301039-CREEPAGE"))
    )
    (comp (ref "ZD1")
      (value "BZX384-C13")
      (footprint "eagle-import:SOD323-W")
      (libsource (lib "eagle-import") (part "ZENER-DIODESOD323"))
    )
    (comp (ref "ZD2")
      (value "BZT52C20-DC")
      (footprint "eagle-import:SOD123")
      (libsource (lib "eagle-import") (part "ZENER-DIODESOD123"))
    )
    (comp (ref "ZD3")
      (value "MMSZ5V1T1G")
      (footprint "eagle-import:SOD323-W")
      (libsource (lib "eagle-import") (part "ZENER-DIODESOD323"))
    )
  )
  (nets
    (net (code "1") (name "+2.5VREF") (class "Default")
      (node (ref "C71") (pin "1") (pinfunction "1_1") (pintype "passive"))
      (node (ref "IC7") (pin "3") (pinfunction "+IN1_3") (pintype "input"))
      (node (ref "P1") (pin "E") (pinfunction "E_E") (pintype "passive"))
      (node (ref "R73") (pin "2") (pinfunction "2_2") (pintype "passive"))
      (node (ref "R77") (pin "1") (pinfunction "1_1") (pintype "passive"))
    )
    (net (code "2") (name "+5VREF") (class "Default")
      (node (ref "R52") (pin "2") (pinfunction "2_2") (pintype "passive"))
      (node (ref "R53") (pin "2") (pinfunction "2_2") (pintype "passive"))
      (node (ref "X3") (pin "1") (pinfunction "1_1") (pintype "passive"))
    )
    (net (code "3") (name "+12V") (class "Default")
      (node (ref "C26") (pin "2") (pinfunction "2_2") (pintype "passive"))
      (node (ref "C27") (pin "2") (pinfunction "2_2") (pintype "passive"))
      (node (ref "C47") (pin "1") (pinfunction "1_1") (pintype "passive"))
      (node (ref "IC4") (pin "8") (pinfunction "V+_8") (pintype "power_in"))
      (node (ref "JP1") (pin "2") (pinfunction "2_2") (pintype "passive"))
      (node (ref "OK2") (pin "1") (pinfunction "A_1") (pintype "passive"))
      (node (ref "R18") (pin "2") (pinfunction "2_2") (pintype "passive"))
      (node (ref "R31") (pin "2") (pinfunction "2_2") (pintype "passive"))
      (node (ref "R40") (pin "2") (pinfunction "2_2") (pintype "passive"))
    )
    (net (code "4") (name "0V") (class "Default")
      (node (ref "C13") (pin "-") (pinfunction "-_-") (pintype "passive"))
      (node (ref "C18") (pin "1") (pinfunction "1_1") (pintype "passive"))
      (node (ref "C21") (pin "2") (pinfunction "-_2") (pintype "passive"))
      (node (ref "C24") (pin "2") (pinfunction "2_2") (pintype "passive"))
      (node (ref "C25") (pin "2") (pinfunction "2_2") (pintype "passive"))
      (node (ref "C26") (pin "1") (pinfunction "1_1") (pintype "passive"))
      (node (ref "C27") (pin "1") (pinfunction "1_1") (pintype "passive"))
      (node (ref "C31") (pin "-") (pinfunction "-_-") (pintype "passive"))
      (node (ref "C32") (pin "-") (pinfunction "-_-") (pintype "passive"))
      (node (ref "C33") (pin "2") (pinfunction "2_2") (pintype "passive"))
      (node (ref "C35") (pin "2") (pinfunction "2_2") (pintype "passive"))
      (node (ref "C36") (pin "2") (pinfunction "2_2") (pintype "passive"))
      (node (ref "C37") (pin "2") (pinfunction "2_2") (pintype "passive"))
      (node (ref "C39") (pin "1") (pinfunction "1_1") (pintype "passive"))
      (node (ref "C41") (pin "2") (pinfunction "2_2") (pintype "passive"))
      (node (ref "C42") (pin "2") (pinfunction "2_2") (pintype "passive"))
      (node (ref "C6") (pin "2") (pinfunction "2_2") (pintype "passive"))
      (node (ref "C7") (pin "2") (pinfunction "-_2") (pintype "passive"))
      (node (ref "C8") (pin "2") (pinfunction "2_2") (pintype "passive"))
      (node (ref "D12") (pin "2") (pinfunction "A_2") (pintype "passive"))
      (node (ref "D8") (pin "A") (pinfunction "A_A") (pintype "passive"))
      (node (ref "IC1") (pin "1") (pinfunction "GND_1") (pintype "passive"))
      (node (ref "IC1") (pin "2") (pinfunction "GND_2") (pintype "passive"))
      (node (ref "IC1") (pin "3") (pinfunction "GND_3") (pintype "passive"))
      (node (ref "IC1") (pin "4") (pinfunction "GND_4") (pintype "passive"))
      (node (ref "IC2") (pin "9") (pinfunction "GNDB_9") (pintype "power_in"))
      (node (ref "JP3") (pin "NO") (pinfunction "NO_NO") (pintype "passive"))
      (node (ref "JP4") (pin "2") (pinfunction "2_2") (pintype "passive"))
      (node (ref "OK1") (pin "3") (pinfunction "EMIT_3") (pintype "passive"))
      (node (ref "Q3") (pin "S") (pinfunction "S_S") (pintype "passive"))
      (node (ref "Q5") (pin "S") (pinfunction "S_S") (pintype "passive"))
      (node (ref "Q6") (pin "S") (pinfunction "S_S") (pintype "passive"))
      (node (ref "R14") (pin "1") (pinfunction "1_1") (pintype "passive"))
      (node (ref "R15") (pin "2") (pinfunction "2_2") (pintype "passive"))
      (node (ref "R16") (pin "2") (pinfunction "2_2") (pintype "passive"))
      (node (ref "R32") (pin "2") (pinfunction "2_2") (pintype "passive"))
      (node (ref "R34") (pin "1") (pinfunction "1_1") (pintype "passive"))
      (node (ref "R34") (pin "2") (pinfunction "2_2") (pintype "passive"))
      (node (ref "SH1") (pin "P$2") (pinfunction "GND_B_P$2") (pintype "bidirectional"))
      (node (ref "TR1") (pin "6") (pinfunction "S_BIAS_6") (pintype "passive"))
      (node (ref "ZD1") (pin "A") (pinfunction "A_A") (pintype "passive"))
      (node (ref "ZD2") (pin "A") (pinfunction "A_A") (pintype "passive"))
    )
    (net (code "5") (name "AC_L_IN") (class "Default")
      (node (ref "C1") (pin "1") (pinfunction "1_1") (pintype "passive"))
      (node (ref "C4A") (pin "2") (pinfunction "2_2") (pintype "passive"))
      (node (ref "L1") (pin "4") (pinfunction "2_4") (pintype "passive"))
      (node (ref "R1") (pin "1") (pinfunction "1_1") (pintype "passive"))
      (node (ref "SAR1") (pin "1") (pinfunction "P$1_1") (pintype "bidirectional"))
      (node (ref "X1") (pin "2") (pinfunction "1_2") (pintype "passive"))
    )
    (net (code "6") (name "AC_N_IN") (class "Default")
      (node (ref "C1") (pin "2") (pinfunction "2_2") (pintype "passive"))
      (node (ref "C5A") (pin "2") (pinfunction "2_2") (pintype "passive"))
      (node (ref "L1") (pin "2") (pinfunction "2_2") (pintype "passive"))
      (node (ref "R2") (pin "2") (pinfunction "2_2") (pintype "passive"))
      (node (ref "SAR2") (pin "1") (pinfunction "P$1_1") (pintype "bidirectional"))
      (node (ref "X1") (pin "3") (pinfunction "1_3") (pintype "passive"))
    )
    (net (code "7") (name "AGND") (class "Default")
      (node (ref "C34") (pin "1") (pinfunction "1_1") (pintype "passive"))
      (node (ref "C40") (pin "2") (pinfunction "2_2") (pintype "passive"))
      (node (ref "C43") (pin "1") (pinfunction "1_1") (pintype "passive"))
      (node (ref "C44") (pin "1") (pinfunction "1_1") (pintype "passive"))
      (node (ref "C45") (pin "1") (pinfunction "1_1") (pintype "passive"))
      (node (ref "C46") (pin "1") (pinfunction "1_1") (pintype "passive"))
      (node (ref "C47") (pin "2") (pinfunction "2_2") (pintype "passive"))
      (node (ref "C48") (pin "1") (pinfunction "1_1") (pintype "passive"))
      (node (ref "IC2") (pin "4") (pinfunction "GNDI_4") (pintype "power_in"))
      (node (ref "IC2") (pin "5") (pinfunction "DISABLE_5") (pintype "input"))
      (node (ref "IC3") (pin "10") (pinfunction "PGND_10") (pintype "power_in"))
      (node (ref "IC3") (pin "11") (pinfunction "AGND_11") (pintype "power_in"))
      (node (ref "IC4") (pin "4") (pinfunction "V-_4") (pintype "power_in"))
      (node (ref "JP4") (pin "1") (pinfunction "1_1") (pintype "passive"))
      (node (ref "OK3") (pin "3") (pinfunction "EMIT_3") (pintype "passive"))
      (node (ref "Q4") (pin "1") (pinfunction "C_1") (pintype "passive"))
      (node (ref "R19") (pin "2") (pinfunction "2_2") (pintype "passive"))
      (node (ref "R20") (pin "2") (pinfunction "2_2") (pintype "passive"))
      (node (ref "R21") (pin "2") (pinfunction "2_2") (pintype "passive"))
      (node (ref "R27") (pin "1") (pinfunction "1_1") (pintype "passive"))
      (node (ref "R27") (pin "2") (pinfunction "2_2") (pintype "passive"))
      (node (ref "R28") (pin "1") (pinfunction "1_1") (pintype "passive"))
      (node (ref "R43") (pin "2") (pinfunction "2_2") (pintype "passive"))
      (node (ref "R46") (pin "2") (pinfunction "2_2") (pintype "passive"))
      (node (ref "R47") (pin "2") (pinfunction "2_2") (pintype "passive"))
      (node (ref "R51") (pin "2") (pinfunction "2_2") (pintype "passive"))
      (node (ref "R55") (pin "2") (pinfunction "2_2") (pintype "passive"))
      (node (ref "R56") (pin "2") (pinfunction "2_2") (pintype "passive"))
      (node (ref "R57") (pin "2") (pinfunction "2_2") (pintype "passive"))
      (node (ref "R58") (pin "2") (pinfunction "2_2") (pintype "passive"))
      (node (ref "TR2") (pin "1") (pinfunction "S_DOT_1") (pintype "passive"))
      (node (ref "ZD4") (pin "A") (pinfunction "A_A") (pintype "passive"))
    )
    (net (code "8") (name "AUX_AC") (class "Default")
      (node (ref "C3") (pin "2") (pinfunction "2_2") (pintype "passive"))
      (node (ref "D1") (pin "A") (pinfunction "A_A") (pintype "passive"))
      (node (ref "D6") (pin "A") (pinfunction "A_A") (pintype "passive"))
      (node (ref "D7") (pin "A") (pinfunction "A_A") (pintype "passive"))
      (node (ref "R11") (pin "2") (pinfunction "2_2") (pintype "passive"))
      (node (ref "TR1") (pin "7") (pinfunction "S_BIAS_DOT_7") (pintype "passive"))
    )
    (net (code "9") (name "BUCK_OUT") (class "Default")
      (node (ref "C28") (pin "2") (pinfunction "2_2") (pintype "passive"))
      (node (ref "C29") (pin "2") (pinfunction "2_2") (pintype "passive"))
      (node (ref "C30") (pin "2") (pinfunction "2_2") (pintype "passive"))
      (node (ref "D12") (pin "1") (pinfunction "C_1") (pintype "passive"))
      (node (ref "IC2") (pin "14") (pinfunction "GNDA_14") (pintype "power_in"))
      (node (ref "L5") (pin "2") (pinfunction "P$2_2") (pintype "bidirectional"))
      (node (ref "L6") (pin "2") (pinfunction "P$2_2") (pintype "bidirectional"))
      (node (ref "Q2") (pin "S") (pinfunction "S_S") (pintype "passive"))
      (node (ref "Q3") (pin "D") (pinfunction "D_D") (pintype "passive"))
    )
    (net (code "10") (name "COMP") (class "Default")
      (node (ref "C46") (pin "2") (pinfunction "2_2") (pintype "passive"))
      (node (ref "IC3") (pin "3") (pinfunction "COMP_3") (pintype "passive"))
      (node (ref "JP8") (pin "1") (pinfunction "1_1") (pintype "passive"))
      (node (ref "R50") (pin "2") (pinfunction "2_2") (pintype "passive"))
    )
    (net (code "11") (name "CT_OUT") (class "Default")
      (node (ref "D9") (pin "C") (pinfunction "C_C") (pintype "passive"))
      (node (ref "R20") (pin "1") (pinfunction "1_1") (pintype "passive"))
      (node (ref "R21") (pin "1") (pinfunction "1_1") (pintype "passive"))
      (node (ref "R49") (pin "1") (pinfunction "1_1") (pintype "passive"))
    )
    (net (code "12") (name "DC_BUS") (class "Default")
      (node (ref "B1") (pin "+") (pinfunction "+_+") (pintype "passive"))
      (node (ref "C12") (pin "1") (pinfunction "1_1") (pintype "passive"))
      (node (ref "C13") (pin "+") (pinfunction "+_+") (pintype "passive"))
      (node (ref "C31") (pin "+") (pinfunction "+_+") (pintype "passive"))
      (node (ref "C32") (pin "+") (pinfunction "+_+") (pintype "passive"))
      (node (ref "C33") (pin "1") (pinfunction "1_1") (pintype "passive"))
      (node (ref "D15") (pin "C") (pinfunction "C_C") (pintype "passive"))
      (node (ref "R30") (pin "1") (pinfunction "1_1") (pintype "passive"))
      (node (ref "R6") (pin "1") (pinfunction "1_1") (pintype "passive"))
      (node (ref "R7") (pin "1") (pinfunction "1_1") (pintype "passive"))
      (node (ref "TR1") (pin "1") (pinfunction "SHIELD_1") (pintype "passive"))
      (node (ref "TR1") (pin "2") (pinfunction "P_2") (pintype "passive"))
      (node (ref "TR2") (pin "7") (pinfunction "P_7") (pintype "passive"))
    )
    (net (code "13") (name "DC_OUT") (class "Default")
      (node (ref "C11") (pin "1") (pinfunction "1_1") (pintype "passive"))
      (node (ref "L2") (pin "2") (pinfunction "2_2") (pintype "passive"))
      (node (ref "X2") (pin "7") (pinfunction "S_7") (pintype "passive"))
    )
    (net (code "14") (name "FB") (class "Default")
      (node (ref "IC3") (pin "2") (pinfunction "FB_2") (pintype "input"))
      (node (ref "R41") (pin "1") (pinfunction "1_1") (pintype "passive"))
      (node (ref "R51") (pin "1") (pinfunction "1_1") (pintype "passive"))
      (node (ref "R54") (pin "1") (pinfunction "1_1") (pintype "passive"))
    )
    (net (code "15") (name "GND") (class "Default")
      (node (ref "C14") (pin "1") (pinfunction "+_1") (pintype "passive"))
      (node (ref "C15") (pin "1") (pinfunction "1_1") (pintype "passive"))
      (node (ref "C17") (pin "2") (pinfunction "2_2") (pintype "passive"))
      (node (ref "C20") (pin "-") (pinfunction "-_-") (pintype "passive"))
      (node (ref "C22") (pin "2") (pinfunction "2_2") (pintype "passive"))
      (node (ref "C49") (pin "-") (pinfunction "-_-") (pintype "passive"))
      (node (ref "C50") (pin "-") (pinfunction "-_-") (pintype "passive"))
      (node (ref "C51") (pin "-") (pinfunction "-_-") (pintype "passive"))
      (node (ref "C52") (pin "2") (pinfunction "2_2") (pintype "passive"))
      (node (ref "C53") (pin "2") (pinfunction "2_2") (pintype "passive"))
      (node (ref "C54") (pin "2") (pinfunction "2_2") (pintype "passive"))
      (node (ref "C55") (pin "2") (pinfunction "2_2") (pintype "passive"))
      (node (ref "C56") (pin "2") (pinfunction "2_2") (pintype "passive"))
      (node (ref "C57") (pin "1") (pinfunction "1_1") (pintype "passive"))
      (node (ref "C58") (pin "2") (pinfunction "2_2") (pintype "passive"))
      (node (ref "C60") (pin "1") (pinfunction "1_1") (pintype "passive"))
      (node (ref "C61") (pin "2") (pinfunction "2_2") (pintype "passive"))
      (node (ref "C62") (pin "2") (pinfunction "2_2") (pintype "passive"))
      (node (ref "C63") (pin "2") (pinfunction "2_2") (pintype "passive"))
      (node (ref "C64") (pin "2") (pinfunction "2_2") (pintype "passive"))
      (node (ref "C65") (pin "2") (pinfunction "2_2") (pintype "passive"))
      (node (ref "C67") (pin "2") (pinfunction "2_2") (pintype "passive"))
      (node (ref "C70") (pin "-") (pinfunction "-_-") (pintype "passive"))
      (node (ref "C71") (pin "2") (pinfunction "2_2") (pintype "passive"))
      (node (ref "C72") (pin "2") (pinfunction "2_2") (pintype "passive"))
      (node (ref "IC5") (pin "6") (pinfunction "VS_6") (pintype "passive"))
      (node (ref "IC5") (pin "7") (pinfunction "GND_7") (pintype "power_in"))
      (node (ref "IC6") (pin "3") (pinfunction "+IN_3") (pintype "input"))
      (node (ref "IC6") (pin "5") (pinfunction "+IN_5") (pintype "input"))
      (node (ref "IC7") (pin "4") (pinfunction "VCC-_4") (pintype "power_in"))
      (node (ref "IC8") (pin "3") (pinfunction "A_3") (pintype "passive"))
      (node (ref "JP2") (pin "NO") (pinfunction "NO_NO") (pintype "passive"))
      (node (ref "OK2") (pin "3") (pinfunction "EMIT_3") (pintype "passive"))
      (node (ref "P1") (pin "A") (pinfunction "A_A") (pintype "passive"))
      (node (ref "PWR") (pin "C") (pinfunction "C_C") (pintype "passive"))
      (node (ref "Q7") (pin "2") (pinfunction "S_2") (pintype "passive"))
      (node (ref "Q8") (pin "2") (pinfunction "S_2") (pintype "passive"))
      (node (ref "R65") (pin "2") (pinfunction "2_2") (pintype "passive"))
      (node (ref "R86") (pin "1") (pinfunction "1_1") (pintype "passive"))
      (node (ref "TP1") (pin "1") (pinfunction "P$1_1") (pintype "bidirectional"))
      (node (ref "TR1") (pin "10") (pinfunction "S1_10") (pintype "passive"))
      (node (ref "TR1") (pin "11") (pinfunction "S1_11") (pintype "passive"))
      (node (ref "TR1") (pin "9") (pinfunction "S2_DOT_9") (pintype "passive"))
      (node (ref "X2") (pin "3") (pinfunction "S_3") (pintype "passive"))
      (node (ref "X4") (pin "2") (pinfunction "1_2") (pintype "passive"))
      (node (ref "ZD3") (pin "A") (pinfunction "A_A") (pintype "passive"))
      (node (ref "ZD5") (pin "A") (pinfunction "A_A") (pintype "passive"))
    )
    (net (code "16") (name "GNDA") (class "Default")
      (node (ref "B1") (pin "-") (pinfunction "-_-") (pintype "passive"))
      (node (ref "SH1") (pin "P$1") (pinfunction "GND_A_P$1") (pintype "bidirectional"))
    )
    (net (code "17") (name "HD") (class "Default")
      (node (ref "IC3") (pin "5") (pinfunction "HD_5") (pintype "output"))
      (node (ref "R23") (pin "2") (pinfunction "2_2") (pintype "passive"))
    )
    (net (code "18") (name "HI_OUT") (class "Default")
      (node (ref "D11") (pin "C") (pinfunction "C_C") (pintype "passive"))
      (node (ref "IC2") (pin "15") (pinfunction "VOA_15") (pintype "output"))
      (node (ref "R22") (pin "2") (pinfunction "2_2") (pintype "passive"))
    )
    (net (code "19") (name "LD") (class "Default")
      (node (ref "IC3") (pin "6") (pinfunction "LD_6") (pintype "output"))
      (node (ref "R24") (pin "2") (pinfunction "2_2") (pintype "passive"))
    )
    (net (code "20") (name "LO_OUT") (class "Default")
      (node (ref "D14") (pin "C") (pinfunction "C_C") (pintype "passive"))
      (node (ref "IC2") (pin "10") (pinfunction "VOB_10") (pintype "output"))
      (node (ref "R29") (pin "1") (pinfunction "1_1") (pintype "passive"))
    )
    (net (code "21") (name "Net-(C3-Pad1)") (class "Default")
      (node (ref "C3") (pin "1") (pinfunction "1_1") (pintype "passive"))
      (node (ref "R3") (pin "2") (pinfunction "2_2") (pintype "passive"))
    )
    (net (code "22") (name "Net-(C6-Pad1)") (class "Default")
      (node (ref "C6") (pin "1") (pinfunction "1_1") (pintype "passive"))
      (node (ref "JP1") (pin "1") (pinfunction "1_1") (pintype "passive"))
      (node (ref "Q1") (pin "E") (pinfunction "E_E") (pintype "passive"))
    )
    (net (code "23") (name "Net-(C7-+)") (class "Default")
      (node (ref "C7") (pin "1") (pinfunction "+_1") (pintype "passive"))
      (node (ref "D1") (pin "C") (pinfunction "C_C") (pintype "passive"))
      (node (ref "Q1") (pin "C") (pinfunction "C_C") (pintype "passive"))
      (node (ref "R3") (pin "1") (pinfunction "1_1") (pintype "passive"))
      (node (ref "R4") (pin "1") (pinfunction "1_1") (pintype "passive"))
    )
    (net (code "24") (name "Net-(C8-Pad1)") (class "Default")
      (node (ref "C8") (pin "1") (pinfunction "1_1") (pintype "passive"))
      (node (ref "Q1") (pin "B") (pinfunction "B_B") (pintype "passive"))
      (node (ref "R4") (pin "2") (pinfunction "2_2") (pintype "passive"))
      (node (ref "ZD1") (pin "C") (pinfunction "C_C") (pintype "passive"))
    )
    (net (code "25") (name "Net-(C9-Pad1)") (class "Default")
      (node (ref "C9") (pin "1") (pinfunction "1_1") (pintype "passive"))
      (node (ref "R5") (pin "2") (pinfunction "2_2") (pintype "passive"))
    )
    (net (code "26") (name "Net-(C10-+)") (class "Default")
      (node (ref "C10") (pin "1") (pinfunction "+_1") (pintype "passive"))
      (node (ref "D2") (pin "C") (pinfunction "C_C") (pintype "passive"))
      (node (ref "L2") (pin "1") (pinfunction "1_1") (pintype "passive"))
      (node (ref "R5") (pin "1") (pinfunction "1_1") (pintype "passive"))
    )
    (net (code "27") (name "Net-(C10--)") (class "Default")
      (node (ref "C10") (pin "2") (pinfunction "-_2") (pintype "passive"))
      (node (ref "C11") (pin "2") (pinfunction "2_2") (pintype "passive"))
      (node (ref "JP2") (pin "COM") (pinfunction "COM_COM") (pintype "passive"))
      (node (ref "TR1") (pin "14") (pinfunction "S3_14") (pintype "passive"))
      (node (ref "X2") (pin "6") (pinfunction "S_6") (pintype "passive"))
    )
    (net (code "28") (name "Net-(C12-Pad2)") (class "Default")
      (node (ref "C12") (pin "2") (pinfunction "2_2") (pintype "passive"))
      (node (ref "D3") (pin "C") (pinfunction "C_C") (pintype "passive"))
      (node (ref "R6") (pin "2") (pinfunction "2_2") (pintype "passive"))
    )
    (net (code "29") (name "Net-(C14--)") (class "Default")
      (node (ref "C14") (pin "2") (pinfunction "-_2") (pintype "passive"))
      (node (ref "D4") (pin "A") (pinfunction "A_A") (pintype "passive"))
      (node (ref "L3") (pin "1") (pinfunction "1_1") (pintype "passive"))
      (node (ref "R9") (pin "1") (pinfunction "1_1") (pintype "passive"))
    )
    (net (code "30") (name "Net-(C16-Pad1)") (class "Default")
      (node (ref "C16") (pin "1") (pinfunction "1_1") (pintype "passive"))
      (node (ref "R9") (pin "2") (pinfunction "2_2") (pintype "passive"))
    )
    (net (code "31") (name "Net-(C17-Pad1)") (class "Default")
      (node (ref "C17") (pin "1") (pinfunction "1_1") (pintype "passive"))
      (node (ref "JP3") (pin "COM") (pinfunction "COM_COM") (pintype "passive"))
    )
    (net (code "32") (name "Net-(C19-Pad1)") (class "Default")
      (node (ref "C19") (pin "1") (pinfunction "1_1") (pintype "passive"))
      (node (ref "R10") (pin "2") (pinfunction "2_2") (pintype "passive"))
    )
    (net (code "33") (name "Net-(C19-Pad2)") (class "Default")
      (node (ref "C19") (pin "2") (pinfunction "2_2") (pintype "passive"))
      (node (ref "D5") (pin "A") (pinfunction "A_A") (pintype "passive"))
      (node (ref "TR1") (pin "12") (pinfunction "S1_DOT_12") (pintype "passive"))
      (node (ref "TR1") (pin "13") (pinfunction "S1_DOT_13") (pintype "passive"))
    )
    (net (code "34") (name "Net-(C20-Pad+)") (class "Default")
      (node (ref "C20") (pin "+") (pinfunction "+_+") (pintype "passive"))
      (node (ref "D5") (pin "C") (pinfunction "C_C") (pintype "passive"))
      (node (ref "L4") (pin "1") (pinfunction "1_1") (pintype "passive"))
      (node (ref "R10") (pin "1") (pinfunction "1_1") (pintype "passive"))
      (node (ref "R13") (pin "1") (pinfunction "1_1") (pintype "passive"))
    )
    (net (code "35") (name "Net-(C21-+)") (class "Default")
      (node (ref "C18") (pin "2") (pinfunction "2_2") (pintype "passive"))
      (node (ref "C21") (pin "1") (pinfunction "+_1") (pintype "passive"))
      (node (ref "D6") (pin "C") (pinfunction "C_C") (pintype "passive"))
      (node (ref "IC1") (pin "5") (pinfunction "VDD_5") (pintype "power_in"))
      (node (ref "ZD2") (pin "C") (pinfunction "C_C") (pintype "passive"))
    )
    (net (code "36") (name "Net-(C23-Pad1)") (class "Default")
      (node (ref "C23") (pin "1") (pinfunction "1_1") (pintype "passive"))
      (node (ref "R16") (pin "1") (pinfunction "1_1") (pintype "passive"))
    )
    (net (code "37") (name "Net-(C38-Pad1)") (class "Default")
      (node (ref "C38") (pin "1") (pinfunction "1_1") (pintype "passive"))
      (node (ref "R26") (pin "1") (pinfunction "1_1") (pintype "passive"))
    )
    (net (code "38") (name "Net-(C39-Pad2)") (class "Default")
      (node (ref "C39") (pin "2") (pinfunction "2_2") (pintype "passive"))
      (node (ref "D16") (pin "1") (pinfunction "C_1") (pintype "passive"))
      (node (ref "D16") (pin "3") (pinfunction "C_3") (pintype "passive"))
      (node (ref "D19") (pin "1") (pinfunction "C_1") (pintype "passive"))
      (node (ref "D19") (pin "3") (pinfunction "C_3") (pintype "passive"))
      (node (ref "R35") (pin "1") (pinfunction "1_1") (pintype "passive"))
      (node (ref "R37") (pin "1") (pinfunction "1_1") (pintype "passive"))
      (node (ref "R42") (pin "2") (pinfunction "2_2") (pintype "passive"))
    )
    (net (code "39") (name "Net-(C40-Pad1)") (class "Default")
      (node (ref "C40") (pin "1") (pinfunction "1_1") (pintype "passive"))
      (node (ref "D18") (pin "A") (pinfunction "A_A") (pintype "passive"))
      (node (ref "R36") (pin "2") (pinfunction "2_2") (pintype "passive"))
      (node (ref "R39") (pin "2") (pinfunction "2_2") (pintype "passive"))
      (node (ref "R43") (pin "1") (pinfunction "1_1") (pintype "passive"))
      (node (ref "TP2") (pin "2") (pinfunction "2_2") (pintype "passive"))
    )
    (net (code "40") (name "Net-(C57-Pad2)") (class "Default")
      (node (ref "C57") (pin "2") (pinfunction "2_2") (pintype "passive"))
      (node (ref "R60") (pin "1") (pinfunction "1_1") (pintype "passive"))
    )
    (net (code "41") (name "Net-(C58-Pad1)") (class "Default")
      (node (ref "C58") (pin "1") (pinfunction "1_1") (pintype "passive"))
      (node (ref "R61") (pin "2") (pinfunction "2_2") (pintype "passive"))
      (node (ref "R62") (pin "2") (pinfunction "2_2") (pintype "passive"))
    )
    (net (code "42") (name "Net-(C63-Pad1)") (class "Default")
      (node (ref "C63") (pin "1") (pinfunction "1_1") (pintype "passive"))
      (node (ref "R67") (pin "2") (pinfunction "2_2") (pintype "passive"))
      (node (ref "R68") (pin "2") (pinfunction "2_2") (pintype "passive"))
    )
    (net (code "43") (name "Net-(C69-Pad2)") (class "Default")
      (node (ref "C69") (pin "2") (pinfunction "2_2") (pintype "passive"))
      (node (ref "R76") (pin "2") (pinfunction "2_2") (pintype "passive"))
    )
    (net (code "44") (name "Net-(C70-Pad+)") (class "Default")
      (node (ref "C70") (pin "+") (pinfunction "+_+") (pintype "passive"))
      (node (ref "R75") (pin "1") (pinfunction "1_1") (pintype "passive"))
      (node (ref "R82") (pin "1") (pinfunction "1_1") (pintype "passive"))
      (node (ref "R83") (pin "1") (pinfunction "1_1") (pintype "passive"))
    )
    (net (code "45") (name "Net-(C74-Pad2)") (class "Default")
      (node (ref "C74") (pin "2") (pinfunction "2_2") (pintype "passive"))
      (node (ref "R85") (pin "1") (pinfunction "1_1") (pintype "passive"))
    )
    (net (code "46") (name "Net-(D7-PadC)") (class "Default")
      (node (ref "D7") (pin "C") (pinfunction "C_C") (pintype "passive"))
      (node (ref "D8") (pin "C") (pinfunction "C_C") (pintype "passive"))
      (node (ref "R12") (pin "2") (pinfunction "2_2") (pintype "passive"))
    )
    (net (code "47") (name "Net-(D10-A)") (class "Default")
      (node (ref "D10") (pin "2") (pinfunction "A_2") (pintype "passive"))
      (node (ref "R18") (pin "1") (pinfunction "1_1") (pintype "passive"))
    )
    (net (code "48") (name "Net-(D11-PadA)") (class "Default")
      (node (ref "D11") (pin "A") (pinfunction "A_A") (pintype "passive"))
      (node (ref "Q2") (pin "G") (pinfunction "G_G") (pintype "passive"))
      (node (ref "R22") (pin "1") (pinfunction "1_1") (pintype "passive"))
    )
    (net (code "49") (name "Net-(D13-PadA)") (class "Default")
      (node (ref "D13") (pin "A") (pinfunction "A_A") (pintype "passive"))
      (node (ref "R31") (pin "1") (pinfunction "1_1") (pintype "passive"))
    )
    (net (code "50") (name "Net-(D14-PadA)") (class "Default")
      (node (ref "D14") (pin "A") (pinfunction "A_A") (pintype "passive"))
      (node (ref "Q3") (pin "G") (pinfunction "G_G") (pintype "passive"))
      (node (ref "R29") (pin "2") (pinfunction "2_2") (pintype "passive"))
      (node (ref "R32") (pin "1") (pinfunction "1_1") (pintype "passive"))
    )
    (net (code "51") (name "Net-(D15-PadA)") (class "Default")
      (node (ref "D15") (pin "A") (pinfunction "A_A") (pintype "passive"))
      (node (ref "R35") (pin "2") (pinfunction "2_2") (pintype "passive"))
      (node (ref "R37") (pin "2") (pinfunction "2_2") (pintype "passive"))
    )
    (net (code "52") (name "Net-(D16-A)") (class "Default")
      (node (ref "D16") (pin "2") (pinfunction "A_2") (pintype "passive"))
      (node (ref "L5") (pin "1") (pinfunction "P$1_1") (pintype "bidirectional"))
      (node (ref "Q5") (pin "D") (pinfunction "D_D") (pintype "passive"))
      (node (ref "R25") (pin "2") (pinfunction "2_2") (pintype "passive"))
      (node (ref "TR3") (pin "P1") (pinfunction "P_P1") (pintype "passive"))
    )
    (net (code "53") (name "Net-(D17-PadA)") (class "Default")
      (node (ref "D17") (pin "A") (pinfunction "A_A") (pintype "passive"))
      (node (ref "R33") (pin "2") (pinfunction "2_2") (pintype "passive"))
    )
    (net (code "54") (name "Net-(D19-A)") (class "Default")
      (node (ref "C38") (pin "2") (pinfunction "2_2") (pintype "passive"))
      (node (ref "D19") (pin "2") (pinfunction "A_2") (pintype "passive"))
      (node (ref "L6") (pin "1") (pinfunction "P$1_1") (pintype "bidirectional"))
      (node (ref "Q6") (pin "D") (pinfunction "D_D") (pintype "passive"))
      (node (ref "TR3") (pin "P1_DOT") (pinfunction "P_DOT_P1_DOT") (pintype "passive"))
    )
    (net (code "55") (name "Net-(D20-PadC)") (class "Default")
      (node (ref "D20") (pin "C") (pinfunction "C_C") (pintype "passive"))
      (node (ref "Q5") (pin "G") (pinfunction "G_G") (pintype "passive"))
      (node (ref "R44") (pin "1") (pinfunction "1_1") (pintype "passive"))
    )
    (net (code "56") (name "Net-(D21-PadC)") (class "Default")
      (node (ref "D21") (pin "C") (pinfunction "C_C") (pintype "passive"))
      (node (ref "Q6") (pin "G") (pinfunction "G_G") (pintype "passive"))
      (node (ref "R48") (pin "1") (pinfunction "1_1") (pintype "passive"))
    )
    (net (code "57") (name "Net-(FAULT-PadA)") (class "Default")
      (node (ref "FAULT") (pin "A") (pinfunction "A_A") (pintype "passive"))
      (node (ref "R69") (pin "2") (pinfunction "2_2") (pintype "passive"))
    )
    (net (code "58") (name "Net-(IC1-BR)") (class "Default")
      (node (ref "IC1") (pin "8") (pinfunction "BR_8") (pintype "input"))
      (node (ref "R15") (pin "1") (pinfunction "1_1") (pintype "passive"))
      (node (ref "R8") (pin "2") (pinfunction "2_2") (pintype "passive"))
    )
    (net (code "59") (name "Net-(IC1-FB)") (class "Default")
      (node (ref "C23") (pin "2") (pinfunction "2_2") (pintype "passive"))
      (node (ref "C25") (pin "1") (pinfunction "1_1") (pintype "passive"))
      (node (ref "IC1") (pin "7") (pinfunction "FB_7") (pintype "input"))
      (node (ref "OK1") (pin "4") (pinfunction "COL_4") (pintype "passive"))
    )
    (net (code "60") (name "Net-(IC1-ZCD)") (class "Default")
      (node (ref "C24") (pin "1") (pinfunction "1_1") (pintype "passive"))
      (node (ref "IC1") (pin "6") (pinfunction "ZCD_6") (pintype "input"))
      (node (ref "R11") (pin "1") (pinfunction "1_1") (pintype "passive"))
      (node (ref "R12") (pin "1") (pinfunction "1_1") (pintype "passive"))
      (node (ref "R14") (pin "2") (pinfunction "2_2") (pintype "passive"))
    )
    (net (code "61") (name "Net-(IC2-DT)") (class "Default")
      (node (ref "IC2") (pin "6") (pinfunction "DT_6") (pintype "input"))
      (node (ref "R28") (pin "2") (pinfunction "2_2") (pintype "passive"))
    )
    (net (code "62") (name "Net-(IC2-VDDA)") (class "Default")
      (node (ref "C28") (pin "1") (pinfunction "1_1") (pintype "passive"))
      (node (ref "C29") (pin "1") (pinfunction "1_1") (pintype "passive"))
      (node (ref "C30") (pin "1") (pinfunction "1_1") (pintype "passive"))
      (node (ref "D10") (pin "1") (pinfunction "C_1") (pintype "passive"))
      (node (ref "D10") (pin "3") (pinfunction "C_3") (pintype "passive"))
      (node (ref "IC2") (pin "16") (pinfunction "VDDA_16") (pintype "power_in"))
    )
    (net (code "63") (name "Net-(IC2-VDDB)") (class "Default")
      (node (ref "C35") (pin "1") (pinfunction "1_1") (pintype "passive"))
      (node (ref "C36") (pin "1") (pinfunction "1_1") (pintype "passive"))
      (node (ref "C37") (pin "1") (pinfunction "1_1") (pintype "passive"))
      (node (ref "D13") (pin "C") (pinfunction "C_C") (pintype "passive"))
      (node (ref "IC2") (pin "11") (pinfunction "VDDB_11") (pintype "power_in"))
    )
    (net (code "64") (name "Net-(IC2-VIA)") (class "Default")
      (node (ref "IC2") (pin "1") (pinfunction "VIA_1") (pintype "input"))
      (node (ref "R23") (pin "1") (pinfunction "1_1") (pintype "passive"))
    )
    (net (code "65") (name "Net-(IC2-VIB)") (class "Default")
      (node (ref "IC2") (pin "2") (pinfunction "VIB_2") (pintype "input"))
      (node (ref "R24") (pin "1") (pinfunction "1_1") (pintype "passive"))
    )
    (net (code "66") (name "Net-(IC3-CS)") (class "Default")
      (node (ref "C45") (pin "2") (pinfunction "2_2") (pintype "passive"))
      (node (ref "IC3") (pin "12") (pinfunction "CS_12") (pintype "input"))
      (node (ref "R49") (pin "2") (pinfunction "2_2") (pintype "passive"))
    )
    (net (code "67") (name "Net-(IC3-REF)") (class "Default")
      (node (ref "C44") (pin "2") (pinfunction "2_2") (pintype "passive"))
      (node (ref "IC3") (pin "4") (pinfunction "REF_4") (pintype "output"))
      (node (ref "R38") (pin "1") (pinfunction "1_1") (pintype "passive"))
      (node (ref "R50") (pin "1") (pinfunction "1_1") (pintype "passive"))
    )
    (net (code "68") (name "Net-(IC3-RT{slash}SYNC)") (class "Default")
      (node (ref "IC3") (pin "15") (pinfunction "RT/SYNC_15") (pintype "input"))
      (node (ref "R47") (pin "1") (pinfunction "1_1") (pintype "passive"))
    )
    (net (code "69") (name "Net-(IC3-SS)") (class "Default")
      (node (ref "C43") (pin "2") (pinfunction "2_2") (pintype "passive"))
      (node (ref "IC3") (pin "13") (pinfunction "SS_13") (pintype "passive"))
    )
    (net (code "70") (name "Net-(IC3-TIME)") (class "Default")
      (node (ref "IC3") (pin "14") (pinfunction "TIME_14") (pintype "input"))
      (node (ref "R46") (pin "1") (pinfunction "1_1") (pintype "passive"))
    )
    (net (code "71") (name "Net-(IC3-UVLO)") (class "Default")
      (node (ref "IC3") (pin "16") (pinfunction "UVLO_16") (pintype "input"))
      (node (ref "R39") (pin "1") (pinfunction "1_1") (pintype "passive"))
      (node (ref "ZD4") (pin "C") (pinfunction "C_C") (pintype "passive"))
    )
    (net (code "72") (name "Net-(IC3-VCC)") (class "Default")
      (node (ref "C41") (pin "1") (pinfunction "1_1") (pintype "passive"))
      (node (ref "C42") (pin "1") (pinfunction "1_1") (pintype "passive"))
      (node (ref "IC3") (pin "1") (pinfunction "VIN_1") (pintype "input"))
      (node (ref "IC3") (pin "7") (pinfunction "VCC_7") (pintype "power_in"))
      (node (ref "R40") (pin "1") (pinfunction "1_1") (pintype "passive"))
    )
    (net (code "73") (name "Net-(IC4A-+IN)") (class "Default")
      (node (ref "C48") (pin "2") (pinfunction "2_2") (pintype "passive"))
      (node (ref "IC4") (pin "3") (pinfunction "+IN_3") (pintype "input"))
      (node (ref "R54") (pin "2") (pinfunction "2_2") (pintype "passive"))
    )
    (net (code "74") (name "Net-(IC4A--IN)") (class "Default")
      (node (ref "IC4") (pin "2") (pinfunction "-IN_2") (pintype "input"))
      (node (ref "R53") (pin "1") (pinfunction "1_1") (pintype "passive"))
      (node (ref "R58") (pin "1") (pinfunction "1_1") (pintype "passive"))
    )
    (net (code "75") (name "Net-(IC4A-OUT)") (class "Default")
      (node (ref "IC4") (pin "1") (pinfunction "OUT_1") (pintype "output"))
      (node (ref "IC4") (pin "7") (pinfunction "OUT_7") (pintype "output"))
      (node (ref "R45") (pin "2") (pinfunction "2_2") (pintype "passive"))
      (node (ref "R55") (pin "1") (pinfunction "1_1") (pintype "passive"))
    )
    (net (code "76") (name "Net-(IC4B-+IN)") (class "Default")
      (node (ref "IC4") (pin "5") (pinfunction "+IN_5") (pintype "input"))
      (node (ref "R57") (pin "1") (pinfunction "1_1") (pintype "passive"))
      (node (ref "X3") (pin "2") (pinfunction "1_2") (pintype "passive"))
    )
    (net (code "77") (name "Net-(IC4B--IN)") (class "Default")
      (node (ref "IC4") (pin "6") (pinfunction "-IN_6") (pintype "input"))
      (node (ref "R52") (pin "1") (pinfunction "1_1") (pintype "passive"))
      (node (ref "R56") (pin "1") (pinfunction "1_1") (pintype "passive"))
    )
    (net (code "78") (name "Net-(IC5-GATE1)") (class "Default")
      (node (ref "D22") (pin "C") (pinfunction "C_C") (pintype "passive"))
      (node (ref "IC5") (pin "1") (pinfunction "GATE1_1") (pintype "output"))
      (node (ref "R63") (pin "2") (pinfunction "2_2") (pintype "passive"))
    )
    (net (code "79") (name "Net-(IC5-GATE2)") (class "Default")
      (node (ref "D23") (pin "C") (pinfunction "C_C") (pintype "passive"))
      (node (ref "IC5") (pin "8") (pinfunction "GATE2_8") (pintype "output"))
      (node (ref "R66") (pin "2") (pinfunction "2_2") (pintype "passive"))
    )
    (net (code "80") (name "Net-(IC5-MOT)") (class "Default")
      (node (ref "IC5") (pin "3") (pinfunction "MOT_3") (pintype "passive"))
      (node (ref "R65") (pin "1") (pinfunction "1_1") (pintype "passive"))
    )
    (net (code "81") (name "Net-(IC5-VCC)") (class "Default")
      (node (ref "C61") (pin "1") (pinfunction "1_1") (pintype "passive"))
      (node (ref "C62") (pin "1") (pinfunction "1_1") (pintype "passive"))
      (node (ref "IC5") (pin "2") (pinfunction "VCC_2") (pintype "power_in"))
      (node (ref "R64") (pin "2") (pinfunction "2_2") (pintype "passive"))
    )
    (net (code "82") (name "Net-(IC6A--IN)") (class "Default")
      (node (ref "C68") (pin "2") (pinfunction "2_2") (pintype "passive"))
      (node (ref "IC6") (pin "2") (pinfunction "-IN_2") (pintype "input"))
      (node (ref "R74") (pin "1") (pinfunction "1_1") (pintype "passive"))
      (node (ref "R75") (pin "2") (pinfunction "2_2") (pintype "passive"))
      (node (ref "R80") (pin "1") (pinfunction "1_1") (pintype "passive"))
    )
    (net (code "83") (name "Net-(IC6A-OUT)") (class "Default")
      (node (ref "C68") (pin "1") (pinfunction "1_1") (pintype "passive"))
      (node (ref "IC6") (pin "1") (pinfunction "OUT_1") (pintype "output"))
      (node (ref "R83") (pin "2") (pinfunction "2_2") (pintype "passive"))
    )
    (net (code "84") (name "Net-(IC6B--IN)") (class "Default")
      (node (ref "IC6") (pin "6") (pinfunction "-IN_6") (pintype "input"))
      (node (ref "R71") (pin "2") (pinfunction "2_2") (pintype "passive"))
      (node (ref "R73") (pin "1") (pinfunction "1_1") (pintype "passive"))
    )
    (net (code "85") (name "Net-(IC6B-OUT)") (class "Default")
      (node (ref "IC6") (pin "7") (pinfunction "OUT_7") (pintype "output"))
      (node (ref "R71") (pin "1") (pinfunction "1_1") (pintype "passive"))
      (node (ref "R74") (pin "2") (pinfunction "2_2") (pintype "passive"))
    )
    (net (code "86") (name "Net-(IC6C-V+)") (class "Default")
      (node (ref "C64") (pin "1") (pinfunction "1_1") (pintype "passive"))
      (node (ref "C65") (pin "1") (pinfunction "1_1") (pintype "passive"))
      (node (ref "IC6") (pin "8") (pinfunction "V+_8") (pintype "power_in"))
      (node (ref "IC7") (pin "8") (pinfunction "VCC+_8") (pintype "power_in"))
      (node (ref "JP5") (pin "2") (pinfunction "2_2") (pintype "passive"))
      (node (ref "R69") (pin "1") (pinfunction "1_1") (pintype "passive"))
      (node (ref "R70") (pin "1") (pinfunction "1_1") (pintype "passive"))
      (node (ref "R77") (pin "2") (pinfunction "2_2") (pintype "passive"))
      (node (ref "R79") (pin "2") (pinfunction "2_2") (pintype "passive"))
    )
    (net (code "87") (name "Net-(IC6C-V-)") (class "Default")
      (node (ref "C67") (pin "1") (pinfunction "1_1") (pintype "passive"))
      (node (ref "IC6") (pin "4") (pinfunction "V-_4") (pintype "power_in"))
      (node (ref "JP6") (pin "1") (pinfunction "1_1") (pintype "passive"))
    )
    (net (code "88") (name "Net-(IC7A--IN1)") (class "Default")
      (node (ref "C66") (pin "2") (pinfunction "2_2") (pintype "passive"))
      (node (ref "IC7") (pin "2") (pinfunction "-IN1_2") (pintype "input"))
      (node (ref "R76") (pin "1") (pinfunction "1_1") (pintype "passive"))
      (node (ref "R81") (pin "1") (pinfunction "1_1") (pintype "passive"))
    )
    (net (code "89") (name "Net-(IC7A-OUT1)") (class "Default")
      (node (ref "C66") (pin "1") (pinfunction "1_1") (pintype "passive"))
      (node (ref "C69") (pin "1") (pinfunction "1_1") (pintype "passive"))
      (node (ref "C73") (pin "1") (pinfunction "1_1") (pintype "passive"))
      (node (ref "C74") (pin "1") (pinfunction "1_1") (pintype "passive"))
      (node (ref "IC7") (pin "1") (pinfunction "OUT1_1") (pintype "output"))
      (node (ref "IC8") (pin "1") (pinfunction "C_1") (pintype "passive"))
      (node (ref "OK3") (pin "2") (pinfunction "C_2") (pintype "passive"))
      (node (ref "R84") (pin "2") (pinfunction "2_2") (pintype "passive"))
    )
    (net (code "90") (name "Net-(IC7B-+IN)") (class "Default")
      (node (ref "C72") (pin "1") (pinfunction "1_1") (pintype "passive"))
      (node (ref "IC7") (pin "5") (pinfunction "+IN_5") (pintype "input"))
      (node (ref "JP7") (pin "COM") (pinfunction "COM_COM") (pintype "passive"))
    )
    (net (code "91") (name "Net-(IC7B--IN)") (class "Default")
      (node (ref "IC7") (pin "6") (pinfunction "-IN_6") (pintype "input"))
      (node (ref "IC7") (pin "7") (pinfunction "OUT_7") (pintype "output"))
      (node (ref "R80") (pin "2") (pinfunction "2_2") (pintype "passive"))
    )
    (net (code "92") (name "Net-(IC8-REF)") (class "Default")
      (node (ref "C73") (pin "2") (pinfunction "2_2") (pintype "passive"))
      (node (ref "IC8") (pin "2") (pinfunction "REF_2") (pintype "passive"))
      (node (ref "R78") (pin "1") (pinfunction "1_1") (pintype "passive"))
      (node (ref "R81") (pin "2") (pinfunction "2_2") (pintype "passive"))
      (node (ref "R82") (pin "2") (pinfunction "2_2") (pintype "passive"))
      (node (ref "R85") (pin "2") (pinfunction "2_2") (pintype "passive"))
      (node (ref "R86") (pin "2") (pinfunction "2_2") (pintype "passive"))
    )
    (net (code "93") (name "Net-(JP7-PadNO)") (class "Default")
      (node (ref "JP7") (pin "NO") (pinfunction "NO_NO") (pintype "passive"))
      (node (ref "P1") (pin "S") (pinfunction "S_S") (pintype "passive"))
    )
    (net (code "94") (name "Net-(L1B-1)") (class "Default")
      (node (ref "B1") (pin "AC2") (pinfunction "AC2_AC2") (pintype "passive"))
      (node (ref "C2") (pin "1") (pinfunction "1_1") (pintype "passive"))
      (node (ref "C5") (pin "2") (pinfunction "2_2") (pintype "passive"))
      (node (ref "L1") (pin "3") (pinfunction "1_3") (pintype "passive"))
      (node (ref "SAR1") (pin "2") (pinfunction "P$2_2") (pintype "bidirectional"))
    )
    (net (code "95") (name "Net-(OK1-A)") (class "Default")
      (node (ref "OK1") (pin "1") (pinfunction "A_1") (pintype "passive"))
      (node (ref "R13") (pin "2") (pinfunction "2_2") (pintype "passive"))
    )
    (net (code "96") (name "Net-(OK1-C)") (class "Default")
      (node (ref "OK1") (pin "2") (pinfunction "C_2") (pintype "passive"))
      (node (ref "R17") (pin "1") (pinfunction "1_1") (pintype "passive"))
      (node (ref "ZD3") (pin "C") (pinfunction "C_C") (pintype "passive"))
    )
    (net (code "97") (name "Net-(OK2-C)") (class "Default")
      (node (ref "OK2") (pin "2") (pinfunction "C_2") (pintype "passive"))
      (node (ref "R33") (pin "1") (pinfunction "1_1") (pintype "passive"))
    )
    (net (code "98") (name "Net-(OK3-A)") (class "Default")
      (node (ref "OK3") (pin "1") (pinfunction "A_1") (pintype "passive"))
      (node (ref "R79") (pin "1") (pinfunction "1_1") (pintype "passive"))
      (node (ref "R84") (pin "1") (pinfunction "1_1") (pintype "passive"))
    )
    (net (code "99") (name "Net-(OK3-COL)") (class "Default")
      (node (ref "JP8") (pin "2") (pinfunction "2_2") (pintype "passive"))
      (node (ref "OK3") (pin "4") (pinfunction "COL_4") (pintype "passive"))
    )
    (net (code "100") (name "Net-(PWR-PadA)") (class "Default")
      (node (ref "PWR") (pin "A") (pinfunction "A_A") (pintype "passive"))
      (node (ref "R70") (pin "2") (pinfunction "2_2") (pintype "passive"))
    )
    (net (code "101") (name "Net-(Q4-A)") (class "Default")
      (node (ref "D17") (pin "C") (pinfunction "C_C") (pintype "passive"))
      (node (ref "D18") (pin "C") (pinfunction "C_C") (pintype "passive"))
      (node (ref "Q4") (pin "3") (pinfunction "A_3") (pintype "passive"))
    )
    (net (code "102") (name "Net-(Q4-G)") (class "Default")
      (node (ref "Q4") (pin "2") (pinfunction "G_2") (pintype "passive"))
      (node (ref "R45") (pin "1") (pinfunction "1_1") (pintype "passive"))
    )
    (net (code "103") (name "Net-(R1-Pad2)") (class "Default")
      (node (ref "R1") (pin "2") (pinfunction "2_2") (pintype "passive"))
      (node (ref "R2") (pin "1") (pinfunction "1_1") (pintype "passive"))
    )
    (net (code "104") (name "Net-(R7-Pad2)") (class "Default")
      (node (ref "R7") (pin "2") (pinfunction "2_2") (pintype "passive"))
      (node (ref "R8") (pin "1") (pinfunction "1_1") (pintype "passive"))
    )
    (net (code "105") (name "Net-(R25-Pad1)") (class "Default")
      (node (ref "R25") (pin "1") (pinfunction "1_1") (pintype "passive"))
      (node (ref "R26") (pin "2") (pinfunction "2_2") (pintype "passive"))
    )
    (net (code "106") (name "Net-(R30-Pad2)") (class "Default")
      (node (ref "R30") (pin "2") (pinfunction "2_2") (pintype "passive"))
      (node (ref "R36") (pin "1") (pinfunction "1_1") (pintype "passive"))
      (node (ref "TP2") (pin "1") (pinfunction "1_1") (pintype "passive"))
    )
    (net (code "107") (name "Net-(R41-Pad2)") (class "Default")
      (node (ref "R41") (pin "2") (pinfunction "2_2") (pintype "passive"))
      (node (ref "R42") (pin "1") (pinfunction "1_1") (pintype "passive"))
    )
    (net (code "108") (name "Net-(R72-Pad1)") (class "Default")
      (node (ref "R72") (pin "1") (pinfunction "1_1") (pintype "passive"))
      (node (ref "R78") (pin "2") (pinfunction "2_2") (pintype "passive"))
    )
    (net (code "109") (name "Net-(SAR2-P$2)") (class "Default")
      (node (ref "B1") (pin "AC1") (pinfunction "AC1_AC1") (pintype "passive"))
      (node (ref "C2") (pin "2") (pinfunction "2_2") (pintype "passive"))
      (node (ref "C4") (pin "2") (pinfunction "2_2") (pintype "passive"))
      (node (ref "L1") (pin "1") (pinfunction "1_1") (pintype "passive"))
      (node (ref "SAR2") (pin "2") (pinfunction "P$2_2") (pintype "bidirectional"))
    )
    (net (code "110") (name "Net-(TR1-P2_DOT)") (class "Default")
      (node (ref "D3") (pin "A") (pinfunction "A_A") (pintype "passive"))
      (node (ref "IC1") (pin "13") (pinfunction "DRAIN_13") (pintype "output"))
      (node (ref "IC1") (pin "14") (pinfunction "DRAIN_14") (pintype "output"))
      (node (ref "IC1") (pin "15") (pinfunction "DRAIN_15") (pintype "output"))
      (node (ref "IC1") (pin "16") (pinfunction "DRAIN_16") (pintype "output"))
      (node (ref "TR1") (pin "4") (pinfunction "P2_DOT_4") (pintype "passive"))
    )
    (net (code "111") (name "Net-(TR1-S2)") (class "Default")
      (node (ref "C16") (pin "2") (pinfunction "2_2") (pintype "passive"))
      (node (ref "D4") (pin "C") (pinfunction "C_C") (pintype "passive"))
      (node (ref "TR1") (pin "8") (pinfunction "S2_8") (pintype "passive"))
    )
    (net (code "112") (name "Net-(TR1-S3_DOT)") (class "Default")
      (node (ref "C9") (pin "2") (pinfunction "2_2") (pintype "passive"))
      (node (ref "D2") (pin "A") (pinfunction "A_A") (pintype "passive"))
      (node (ref "TR1") (pin "15") (pinfunction "S3_DOT_15") (pintype "passive"))
    )
    (net (code "113") (name "Net-(TR2-P_DOT)") (class "Default")
      (node (ref "Q2") (pin "D") (pinfunction "D_D") (pintype "passive"))
      (node (ref "TR2") (pin "8") (pinfunction "P_DOT_8") (pintype "passive"))
    )
    (net (code "114") (name "Net-(TR2-S)") (class "Default")
      (node (ref "D9") (pin "A") (pinfunction "A_A") (pintype "passive"))
      (node (ref "R19") (pin "1") (pinfunction "1_1") (pintype "passive"))
      (node (ref "TR2") (pin "3") (pinfunction "S_3") (pintype "passive"))
    )
    (net (code "115") (name "Net-(X2E-S)") (class "Default")
      (node (ref "D24") (pin "A") (pinfunction "A_A") (pintype "passive"))
      (node (ref "X2") (pin "5") (pinfunction "S_5") (pintype "passive"))
    )
    (net (code "116") (name "PE") (class "Default")
      (node (ref "C4") (pin "1") (pinfunction "1_1") (pintype "passive"))
      (node (ref "C4A") (pin "1") (pinfunction "1_1") (pintype "passive"))
      (node (ref "C5") (pin "1") (pinfunction "1_1") (pintype "passive"))
      (node (ref "C59") (pin "2") (pinfunction "2_2") (pintype "passive"))
      (node (ref "C5A") (pin "1") (pinfunction "1_1") (pintype "passive"))
      (node (ref "C60") (pin "2") (pinfunction "2_2") (pintype "passive"))
      (node (ref "JP3") (pin "NC") (pinfunction "NC_NC") (pintype "passive"))
      (node (ref "X1") (pin "1") (pinfunction "1_1") (pintype "passive"))
      (node (ref "X2") (pin "1") (pinfunction "S_1") (pintype "passive"))
    )
    (net (code "117") (name "POUT+") (class "Default")
      (node (ref "C49") (pin "+") (pinfunction "+_+") (pintype "passive"))
      (node (ref "C50") (pin "+") (pinfunction "+_+") (pintype "passive"))
      (node (ref "C51") (pin "+") (pinfunction "+_+") (pintype "passive"))
      (node (ref "C52") (pin "1") (pinfunction "1_1") (pintype "passive"))
      (node (ref "L7") (pin "1") (pinfunction "1_1") (pintype "passive"))
      (node (ref "R59") (pin "1") (pinfunction "1_1") (pintype "passive"))
      (node (ref "R72") (pin "2") (pinfunction "2_2") (pintype "passive"))
      (node (ref "SH2") (pin "P$2") (pinfunction "GND_B_P$2") (pintype "bidirectional"))
      (node (ref "SH3") (pin "P$1") (pinfunction "GND_A_P$1") (pintype "bidirectional"))
    )
    (net (code "118") (name "PREG_OUT+") (class "Default")
      (node (ref "C53") (pin "1") (pinfunction "1_1") (pintype "passive"))
      (node (ref "C54") (pin "1") (pinfunction "1_1") (pintype "passive"))
      (node (ref "C55") (pin "1") (pinfunction "1_1") (pintype "passive"))
      (node (ref "C56") (pin "1") (pinfunction "1_1") (pintype "passive"))
      (node (ref "C59") (pin "1") (pinfunction "1_1") (pintype "passive"))
      (node (ref "JP2") (pin "NC") (pinfunction "NC_NC") (pintype "passive"))
      (node (ref "L7") (pin "2") (pinfunction "2_2") (pintype "passive"))
      (node (ref "R59") (pin "2") (pinfunction "2_2") (pintype "passive"))
      (node (ref "R60") (pin "2") (pinfunction "2_2") (pintype "passive"))
      (node (ref "X4") (pin "1") (pinfunction "1_1") (pintype "passive"))
      (node (ref "ZD5") (pin "C") (pinfunction "C_C") (pintype "passive"))
    )
    (net (code "119") (name "PULL") (class "Default")
      (node (ref "D21") (pin "A") (pinfunction "A_A") (pintype "passive"))
      (node (ref "IC3") (pin "9") (pinfunction "PULL_9") (pintype "output"))
      (node (ref "R48") (pin "2") (pinfunction "2_2") (pintype "passive"))
    )
    (net (code "120") (name "PUSH") (class "Default")
      (node (ref "D20") (pin "A") (pinfunction "A_A") (pintype "passive"))
      (node (ref "IC3") (pin "8") (pinfunction "PUSH_8") (pintype "output"))
      (node (ref "R44") (pin "2") (pinfunction "2_2") (pintype "passive"))
    )
    (net (code "121") (name "REF") (class "Default")
      (node (ref "C34") (pin "2") (pinfunction "2_2") (pintype "passive"))
      (node (ref "IC2") (pin "3") (pinfunction "VDDI_3") (pintype "power_in"))
      (node (ref "IC2") (pin "8") (pinfunction "VDDI_8") (pintype "power_in"))
      (node (ref "R38") (pin "2") (pinfunction "2_2") (pintype "passive"))
    )
    (net (code "122") (name "S1_DOT_OUT") (class "Default")
      (node (ref "IC5") (pin "4") (pinfunction "VD1_4") (pintype "passive"))
      (node (ref "Q7") (pin "3") (pinfunction "D_3") (pintype "passive"))
      (node (ref "R61") (pin "1") (pinfunction "1_1") (pintype "passive"))
      (node (ref "R62") (pin "1") (pinfunction "1_1") (pintype "passive"))
      (node (ref "TR3") (pin "S1_DOT") (pinfunction "S1_DOT_S1_DOT") (pintype "passive"))
    )
    (net (code "123") (name "S1_OUT") (class "Default")
      (node (ref "SH2") (pin "P$1") (pinfunction "GND_A_P$1") (pintype "bidirectional"))
      (node (ref "TR3") (pin "S1") (pinfunction "S1_S1") (pintype "passive"))
    )
    (net (code "124") (name "S2_DOT_OUT") (class "Default")
      (node (ref "SH3") (pin "P$2") (pinfunction "GND_B_P$2") (pintype "bidirectional"))
      (node (ref "TR3") (pin "S2_DOT") (pinfunction "S2_DOT_S2_DOT") (pintype "passive"))
    )
    (net (code "125") (name "S2_OUT") (class "Default")
      (node (ref "IC5") (pin "5") (pinfunction "VD2_5") (pintype "passive"))
      (node (ref "Q8") (pin "3") (pinfunction "D_3") (pintype "passive"))
      (node (ref "R67") (pin "1") (pinfunction "1_1") (pintype "passive"))
      (node (ref "R68") (pin "1") (pinfunction "1_1") (pintype "passive"))
      (node (ref "TR3") (pin "S2") (pinfunction "S2_S2") (pintype "passive"))
    )
    (net (code "126") (name "SR_OUT1") (class "Default")
      (node (ref "D22") (pin "A") (pinfunction "A_A") (pintype "passive"))
      (node (ref "Q7") (pin "1") (pinfunction "G_1") (pintype "passive"))
      (node (ref "R63") (pin "1") (pinfunction "1_1") (pintype "passive"))
    )
    (net (code "127") (name "SR_OUT2") (class "Default")
      (node (ref "D23") (pin "A") (pinfunction "A_A") (pintype "passive"))
      (node (ref "Q8") (pin "1") (pinfunction "G_1") (pintype "passive"))
      (node (ref "R66") (pin "1") (pinfunction "1_1") (pintype "passive"))
    )
    (net (code "128") (name "U_MON") (class "Default")
      (node (ref "JP7") (pin "NC") (pinfunction "NC_NC") (pintype "passive"))
      (node (ref "X2") (pin "8") (pinfunction "S_8") (pintype "passive"))
    )
    (net (code "129") (name "V+") (class "Default")
      (node (ref "C22") (pin "1") (pinfunction "1_1") (pintype "passive"))
      (node (ref "JP5") (pin "1") (pinfunction "1_1") (pintype "passive"))
      (node (ref "L4") (pin "2") (pinfunction "2_2") (pintype "passive"))
      (node (ref "R17") (pin "2") (pinfunction "2_2") (pintype "passive"))
      (node (ref "R64") (pin "1") (pinfunction "1_1") (pintype "passive"))
      (node (ref "X2") (pin "4") (pinfunction "S_4") (pintype "passive"))
    )
    (net (code "130") (name "V-") (class "Default")
      (node (ref "C15") (pin "2") (pinfunction "2_2") (pintype "passive"))
      (node (ref "JP6") (pin "2") (pinfunction "2_2") (pintype "passive"))
      (node (ref "L3") (pin "2") (pinfunction "2_2") (pintype "passive"))
      (node (ref "X2") (pin "2") (pinfunction "S_2") (pintype "passive"))
    )
    (net (code "131") (name "~{FAULT}") (class "Default")
      (node (ref "D24") (pin "C") (pinfunction "C_C") (pintype "passive"))
      (node (ref "FAULT") (pin "C") (pinfunction "C_C") (pintype "passive"))
      (node (ref "OK2") (pin "4") (pinfunction "COL_4") (pintype "passive"))
    )
  )
)
